# audio_board.net
KiCad netlist of a schematic drawn in EAGLE
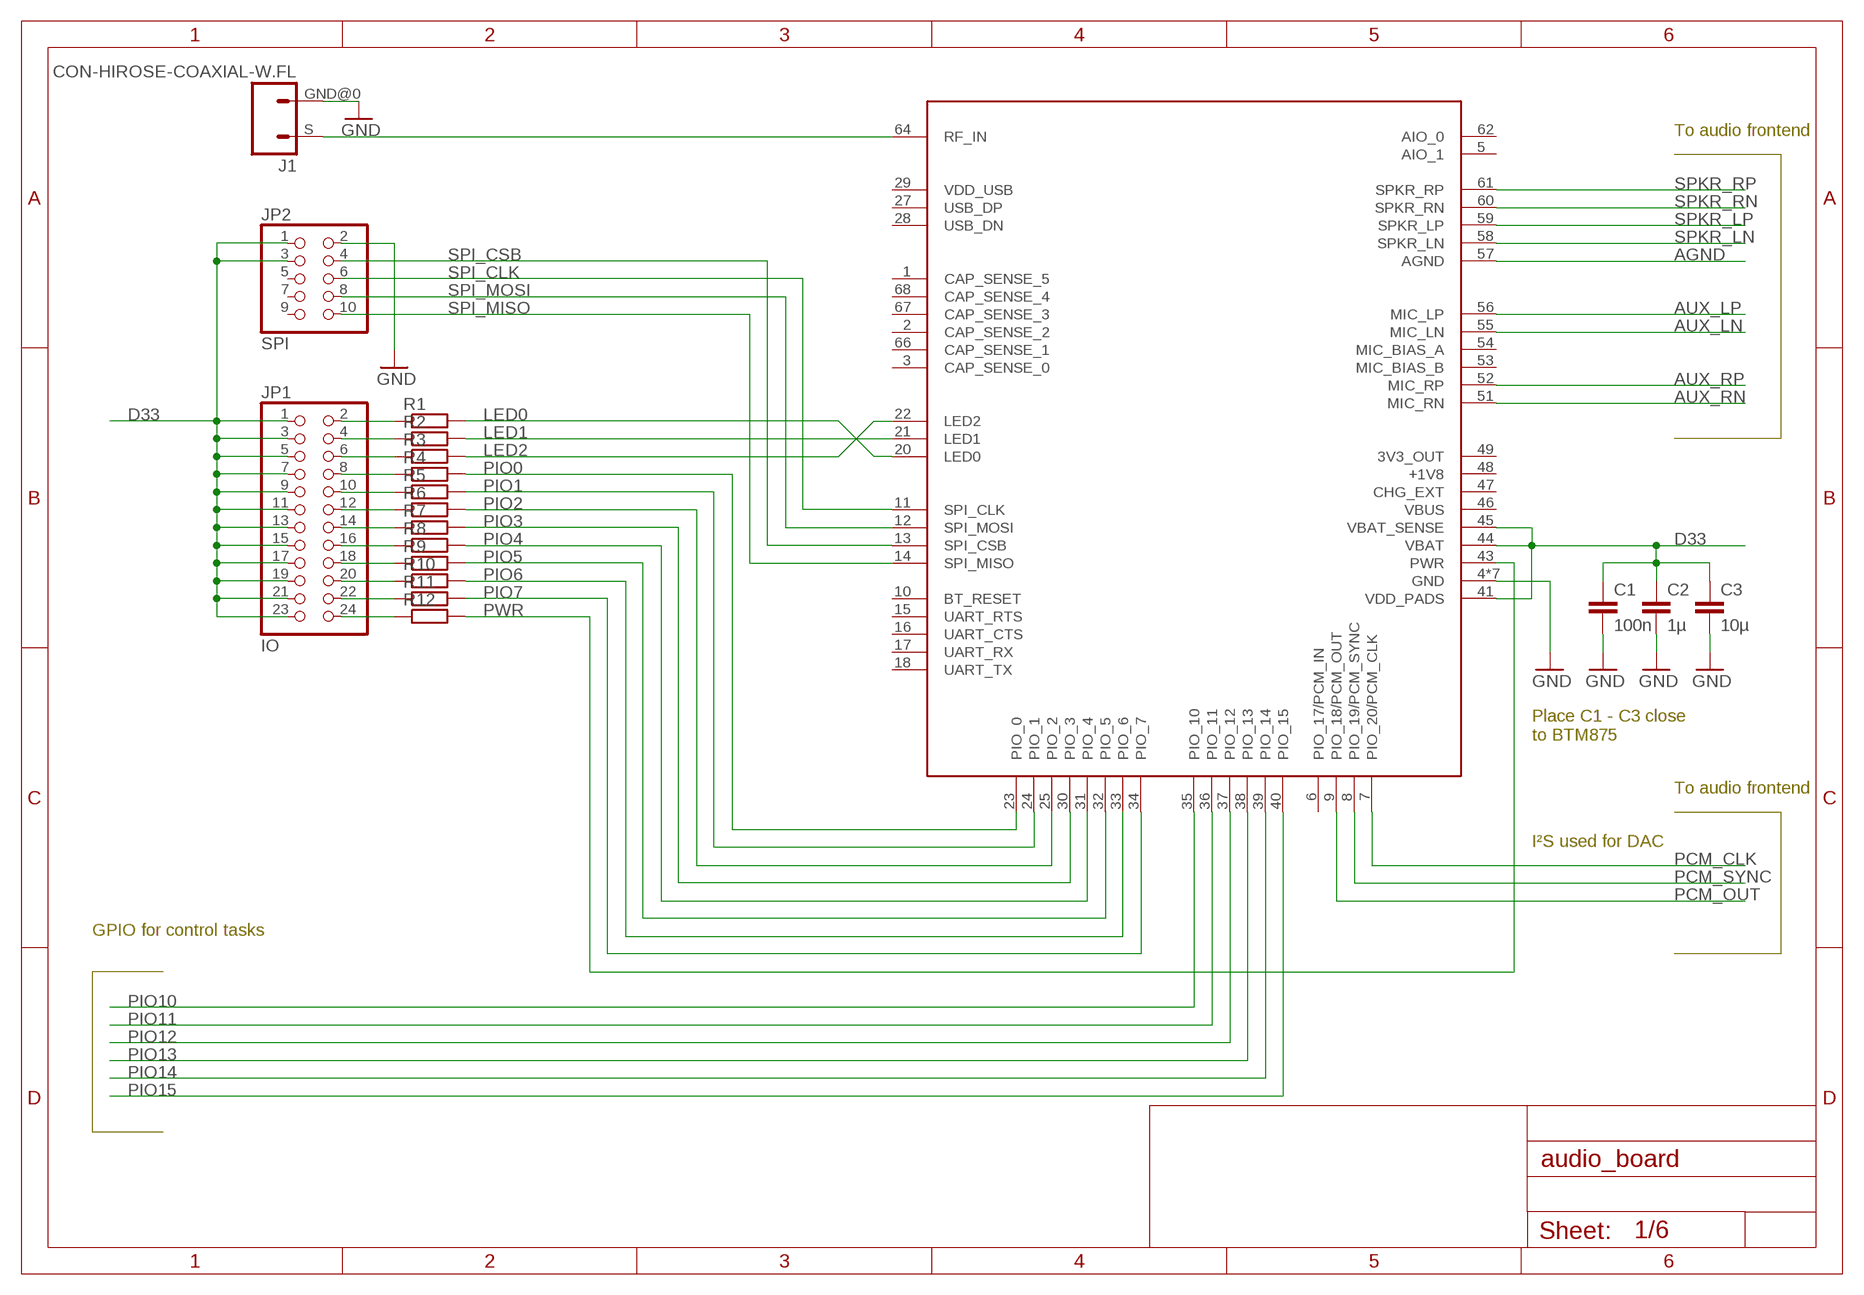
[diagram p0: schematic, sheet 1]
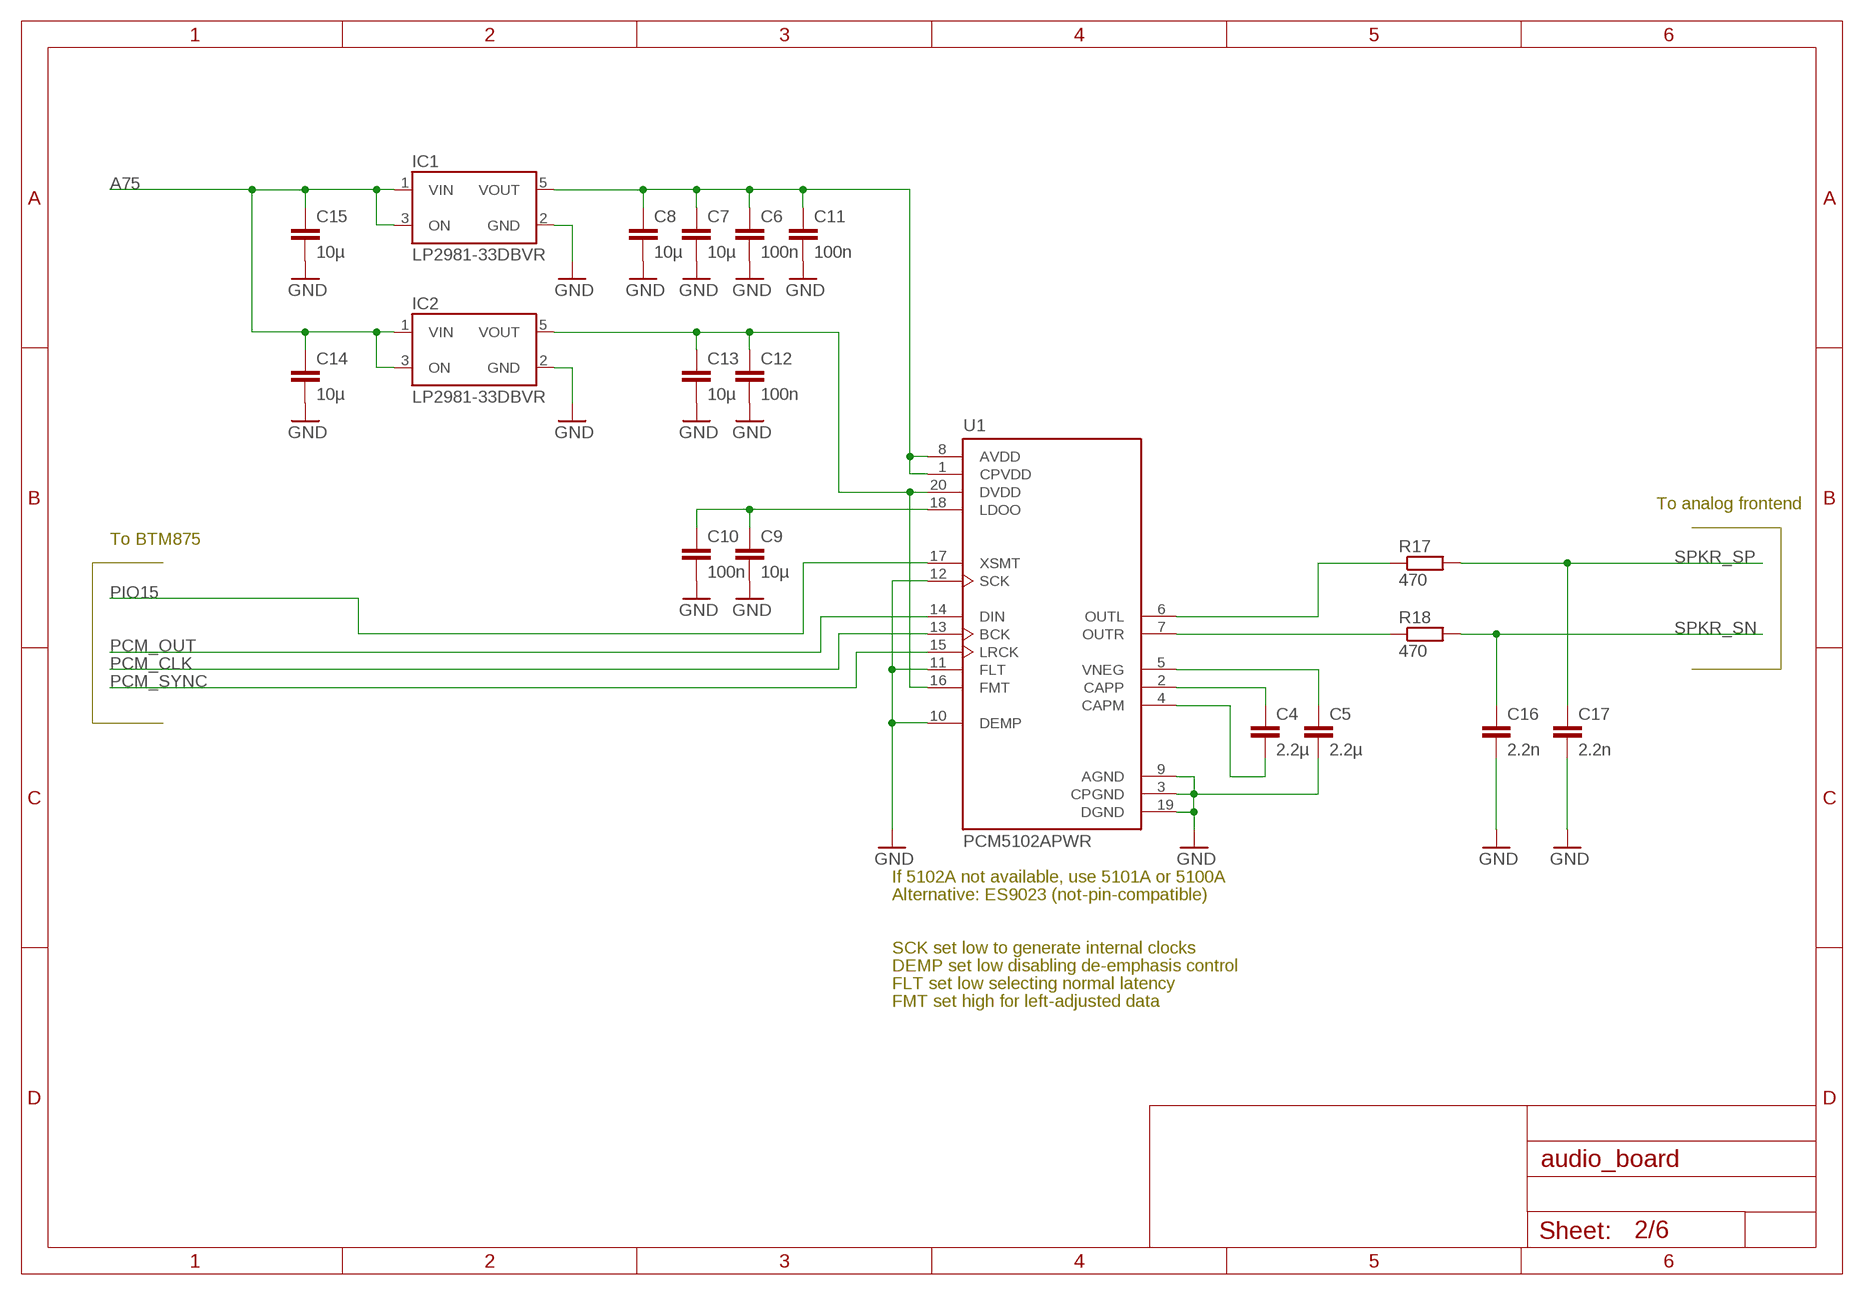
[diagram p1: schematic, sheet 2]
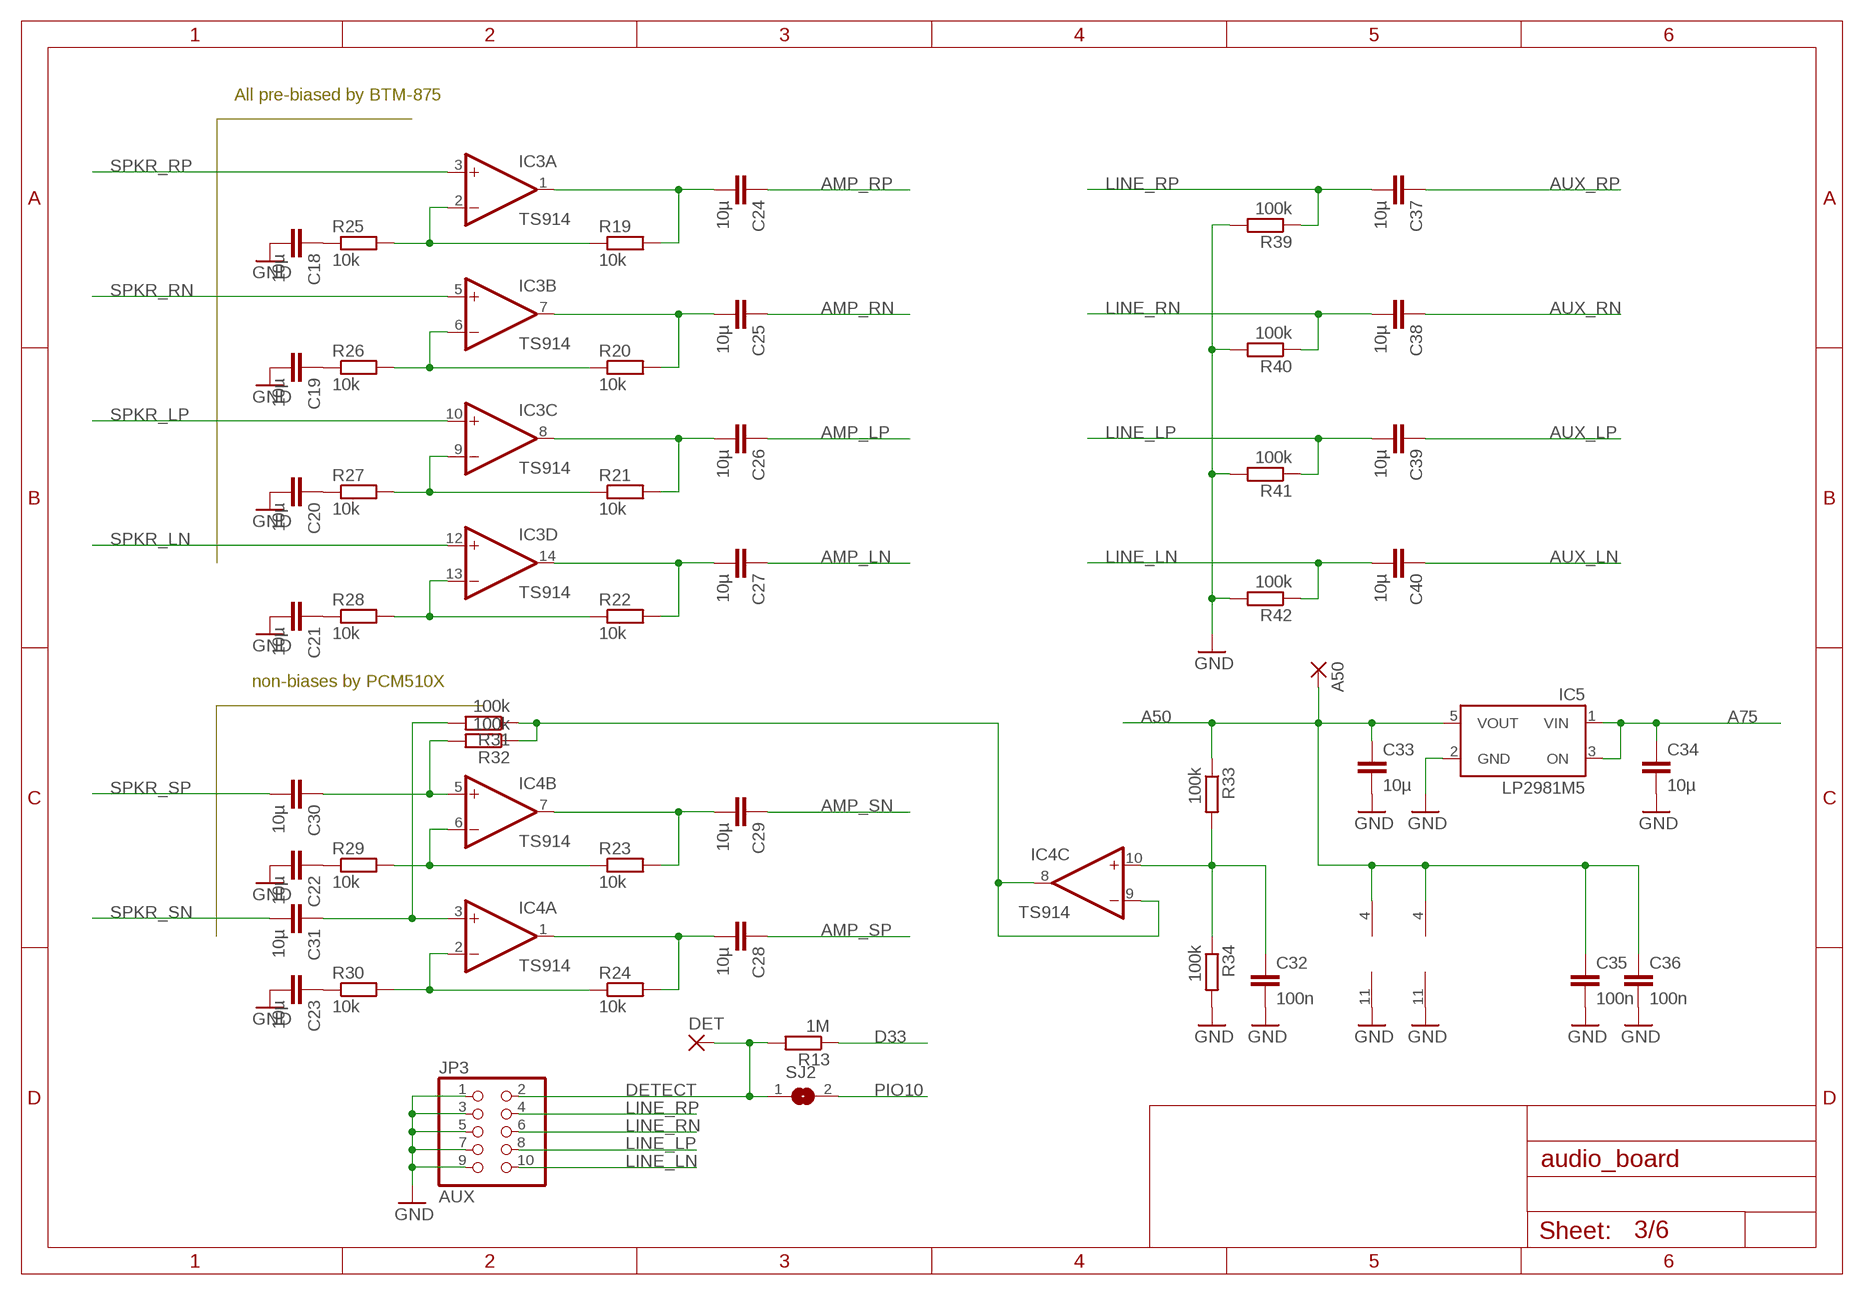
[diagram p2: schematic, sheet 3]
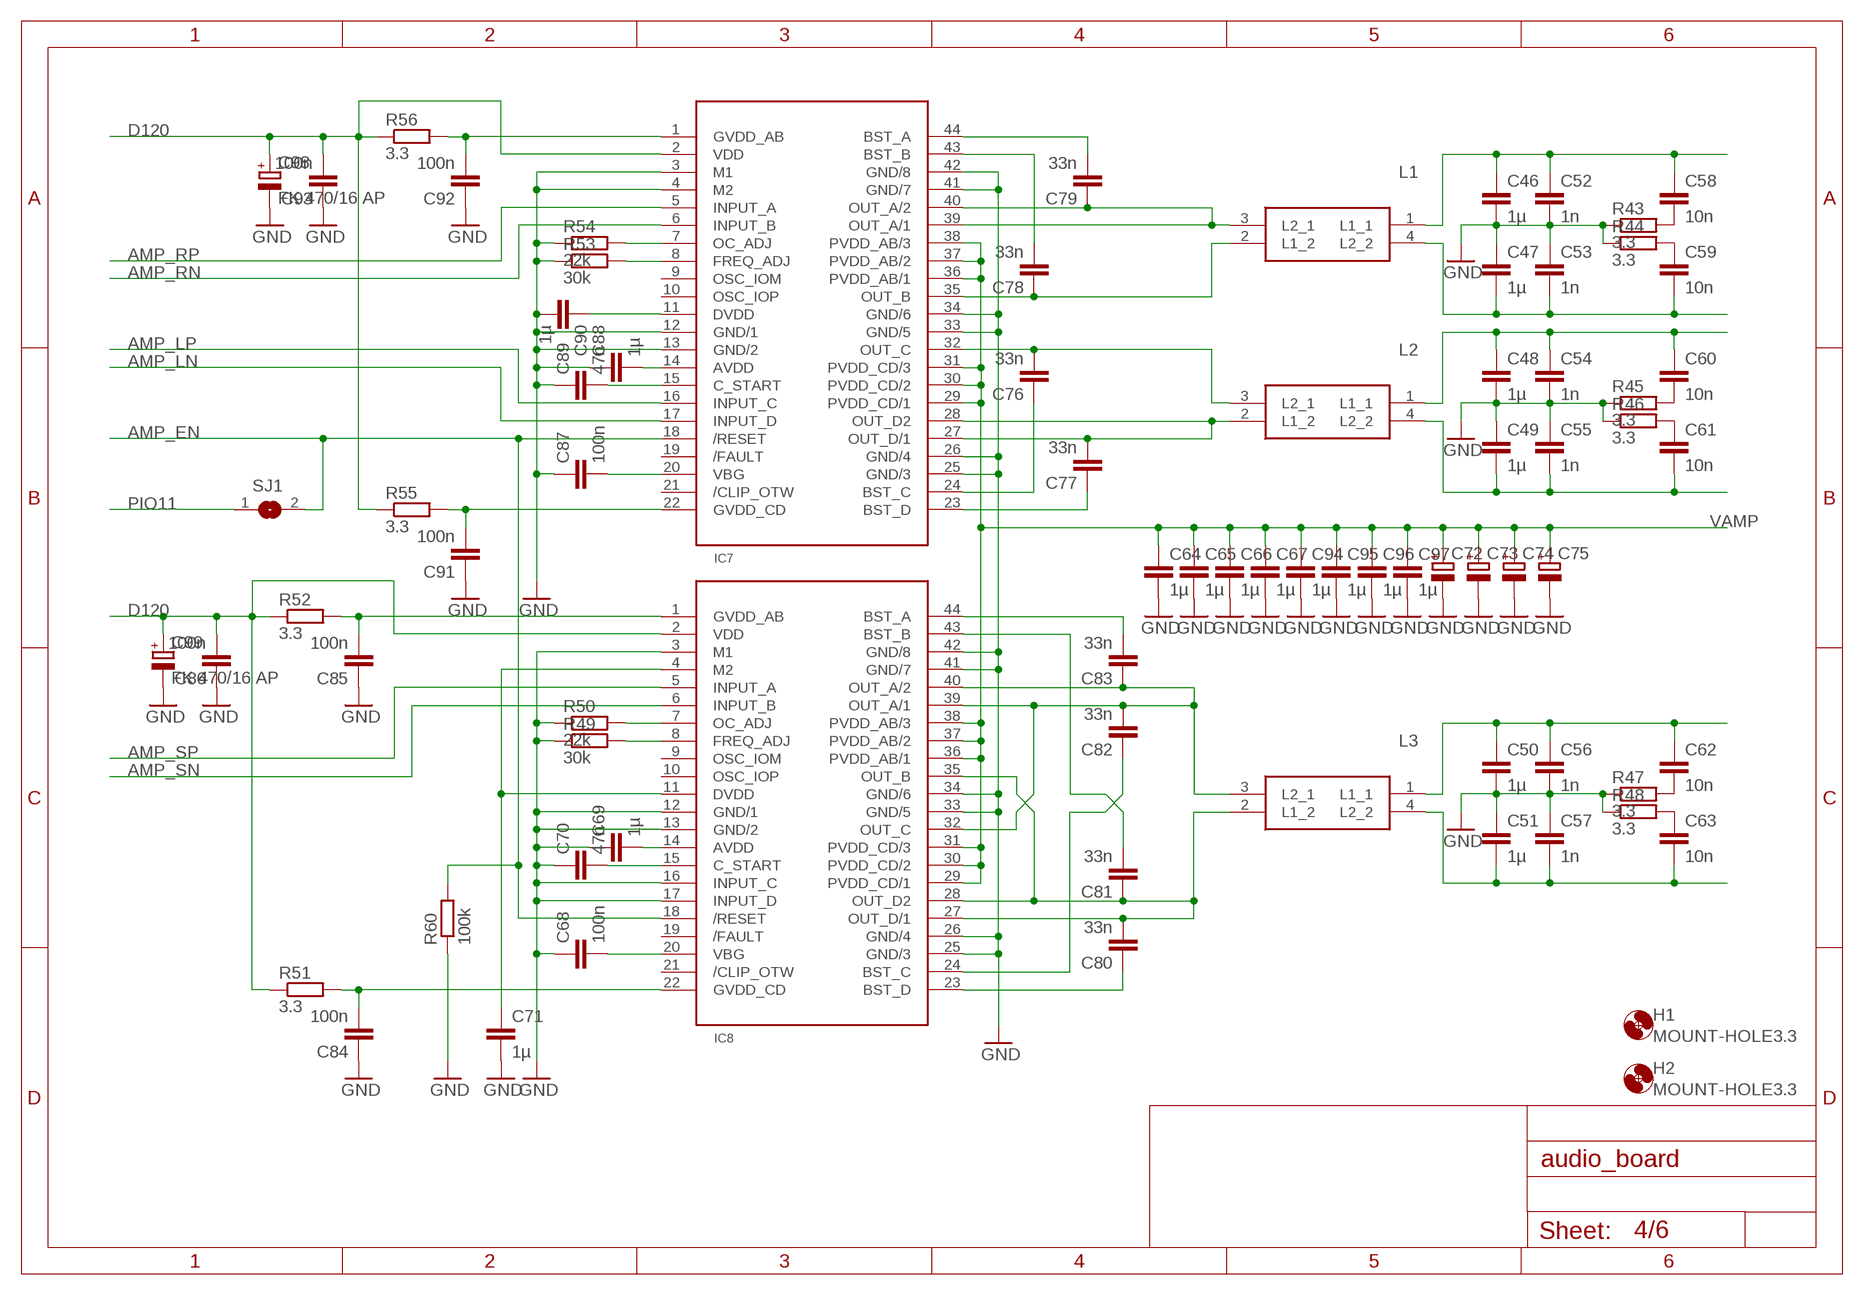
[diagram p3: schematic, sheet 4]
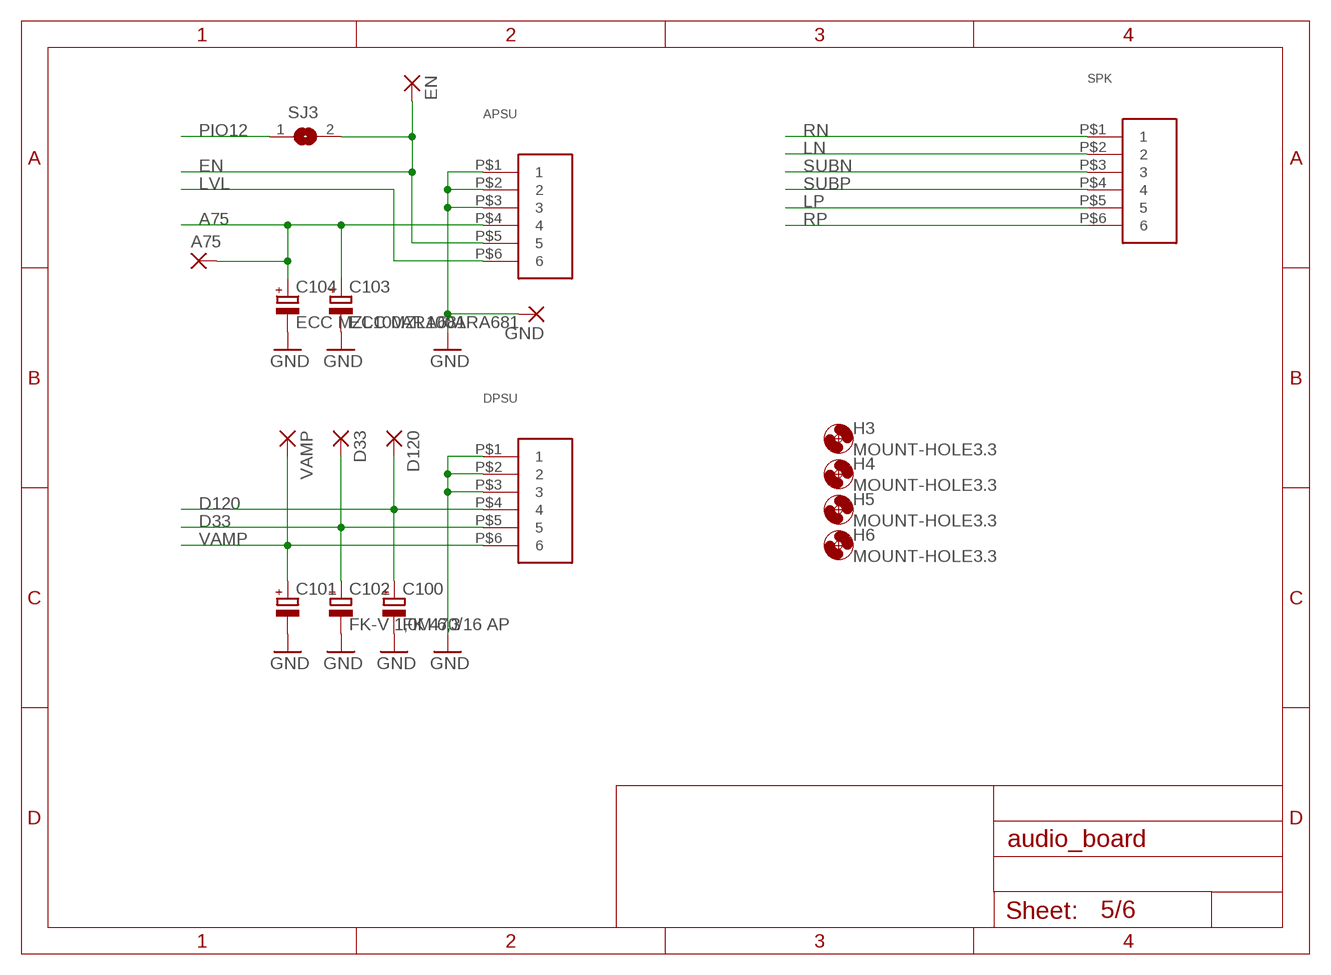
[diagram p4: schematic, sheet 5]
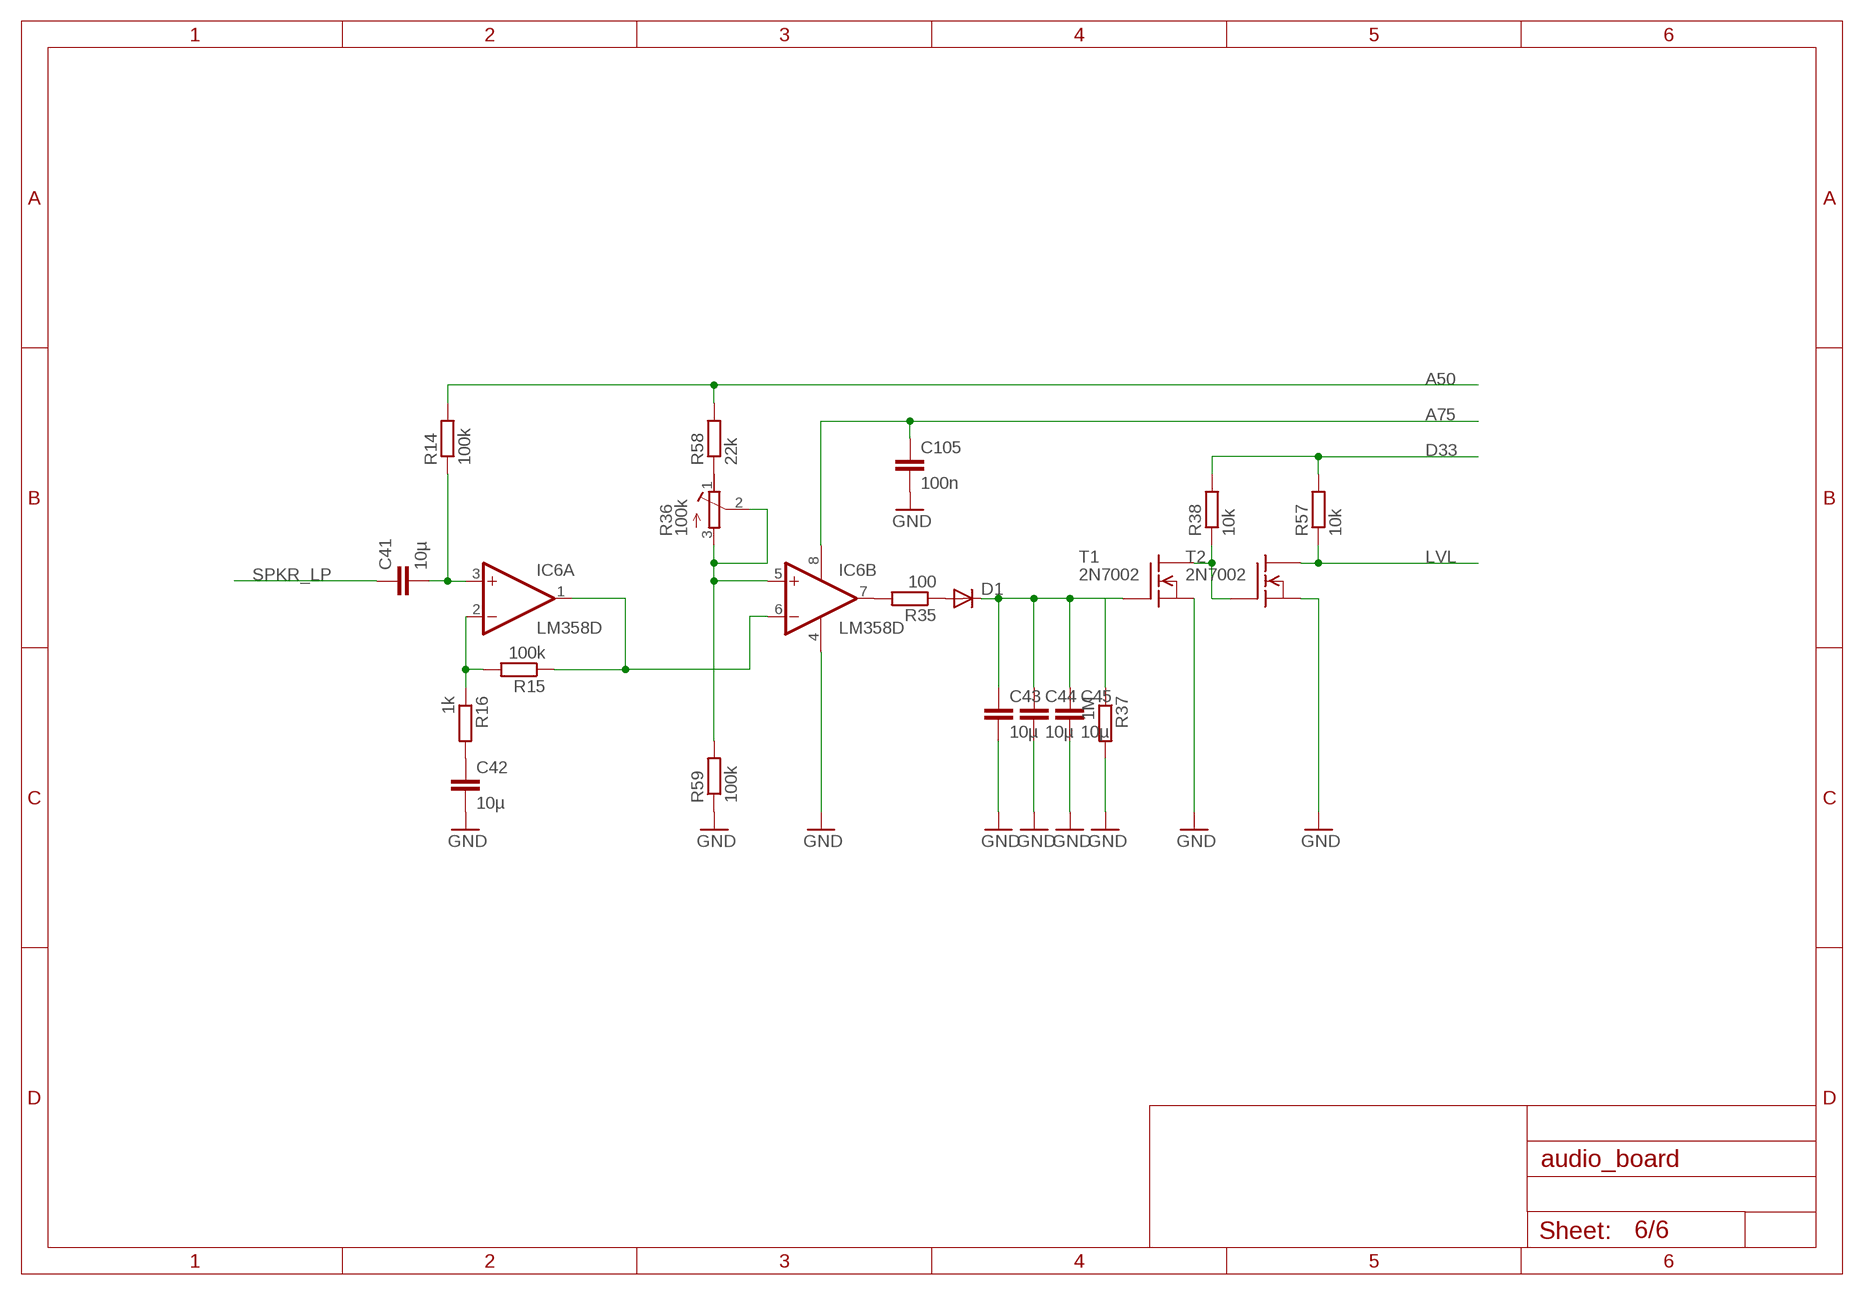
[diagram p5: schematic, sheet 6]

(export (version "E")
  (design (tool "Eeschema 10.0.6"))
  (components
    (comp (ref "C41")
      (value "10µ")
      (footprint "eagle-import:C0805")
      (libsource (lib "eagle-import") (part "C-EUC0805"))
    )
    (comp (ref "C42")
      (value "10µ")
      (footprint "eagle-import:C0805")
      (libsource (lib "eagle-import") (part "C-EUC0805"))
    )
    (comp (ref "C43")
      (value "10µ")
      (footprint "eagle-import:C0805")
      (libsource (lib "eagle-import") (part "C-EUC0805"))
    )
    (comp (ref "C44")
      (value "10µ")
      (footprint "eagle-import:C0805")
      (libsource (lib "eagle-import") (part "C-EUC0805"))
    )
    (comp (ref "C45")
      (value "10µ")
      (footprint "eagle-import:C0805")
      (libsource (lib "eagle-import") (part "C-EUC0805"))
    )
    (comp (ref "C105")
      (value "100n")
      (footprint "eagle-import:C0805")
      (libsource (lib "eagle-import") (part "C-EUC0805"))
    )
    (comp (ref "D1")
      (value "DIODE-DO214AC")
      (footprint "eagle-import:DO214AC")
      (libsource (lib "eagle-import") (part "DIODE-DO214AC"))
    )
    (comp (ref "IC6")
      (value "LM358D")
      (footprint "eagle-import:SO08")
      (libsource (lib "eagle-import") (part "LM358D"))
    )
    (comp (ref "R14")
      (value "100k")
      (footprint "eagle-import:M0805")
      (libsource (lib "eagle-import") (part "R-EU_M0805"))
    )
    (comp (ref "R15")
      (value "100k")
      (footprint "eagle-import:M0805")
      (libsource (lib "eagle-import") (part "R-EU_M0805"))
    )
    (comp (ref "R16")
      (value "1k")
      (footprint "eagle-import:M0805")
      (libsource (lib "eagle-import") (part "R-EU_M0805"))
    )
    (comp (ref "R35")
      (value "100")
      (footprint "eagle-import:M0805")
      (libsource (lib "eagle-import") (part "R-EU_M0805"))
    )
    (comp (ref "R36")
      (value "100k")
      (footprint "eagle-import:RTRIM3314G")
      (libsource (lib "eagle-import") (part "R-TRIMM3314G"))
    )
    (comp (ref "R37")
      (value "1M")
      (footprint "eagle-import:M0805")
      (libsource (lib "eagle-import") (part "R-EU_M0805"))
    )
    (comp (ref "R38")
      (value "10k")
      (footprint "eagle-import:M0805")
      (libsource (lib "eagle-import") (part "R-EU_M0805"))
    )
    (comp (ref "R57")
      (value "10k")
      (footprint "eagle-import:M0805")
      (libsource (lib "eagle-import") (part "R-EU_M0805"))
    )
    (comp (ref "R58")
      (value "22k")
      (footprint "eagle-import:M0805")
      (libsource (lib "eagle-import") (part "R-EU_M0805"))
    )
    (comp (ref "R59")
      (value "100k")
      (footprint "eagle-import:M0805")
      (libsource (lib "eagle-import") (part "R-EU_M0805"))
    )
    (comp (ref "T1")
      (value "2N7002")
      (footprint "eagle-import:SOT23")
      (libsource (lib "eagle-import") (part "2N7002"))
    )
    (comp (ref "T2")
      (value "2N7002")
      (footprint "eagle-import:SOT23")
      (libsource (lib "eagle-import") (part "2N7002"))
    )
    (comp (ref "BT1")
      (value "BTM875-B")
      (footprint "eagle-import:BTM875")
      (libsource (lib "eagle-import") (part "BTM875-B"))
    )
    (comp (ref "C1")
      (value "100n")
      (footprint "eagle-import:C0805")
      (libsource (lib "eagle-import") (part "C-EUC0805"))
    )
    (comp (ref "C2")
      (value "1µ")
      (footprint "eagle-import:C0805")
      (libsource (lib "eagle-import") (part "C-EUC0805"))
    )
    (comp (ref "C3")
      (value "10µ")
      (footprint "eagle-import:C0805")
      (libsource (lib "eagle-import") (part "C-EUC0805"))
    )
    (comp (ref "J1")
      (value "CON-HIROSE-COAXIAL-W.FL")
      (footprint "eagle-import:CON-W.FL")
      (libsource (lib "eagle-import") (part "CON-HIROSE-COAXIAL-W.FL"))
    )
    (comp (ref "JP1")
      (value "IO")
      (footprint "eagle-import:2X12")
      (libsource (lib "eagle-import") (part "PINHD-2X12"))
    )
    (comp (ref "JP2")
      (value "SPI")
      (footprint "eagle-import:2X05")
      (libsource (lib "eagle-import") (part "PINHD-2X5"))
    )
    (comp (ref "R1")
      (value "R-EU_R0805")
      (footprint "eagle-import:R0805")
      (libsource (lib "eagle-import") (part "R-EU_R0805"))
    )
    (comp (ref "R2")
      (value "R-EU_R0805")
      (footprint "eagle-import:R0805")
      (libsource (lib "eagle-import") (part "R-EU_R0805"))
    )
    (comp (ref "R3")
      (value "R-EU_R0805")
      (footprint "eagle-import:R0805")
      (libsource (lib "eagle-import") (part "R-EU_R0805"))
    )
    (comp (ref "R4")
      (value "R-EU_R0805")
      (footprint "eagle-import:R0805")
      (libsource (lib "eagle-import") (part "R-EU_R0805"))
    )
    (comp (ref "R5")
      (value "R-EU_R0805")
      (footprint "eagle-import:R0805")
      (libsource (lib "eagle-import") (part "R-EU_R0805"))
    )
    (comp (ref "R6")
      (value "R-EU_R0805")
      (footprint "eagle-import:R0805")
      (libsource (lib "eagle-import") (part "R-EU_R0805"))
    )
    (comp (ref "R7")
      (value "R-EU_R0805")
      (footprint "eagle-import:R0805")
      (libsource (lib "eagle-import") (part "R-EU_R0805"))
    )
    (comp (ref "R8")
      (value "R-EU_R0805")
      (footprint "eagle-import:R0805")
      (libsource (lib "eagle-import") (part "R-EU_R0805"))
    )
    (comp (ref "R9")
      (value "R-EU_R0805")
      (footprint "eagle-import:R0805")
      (libsource (lib "eagle-import") (part "R-EU_R0805"))
    )
    (comp (ref "R10")
      (value "R-EU_R0805")
      (footprint "eagle-import:R0805")
      (libsource (lib "eagle-import") (part "R-EU_R0805"))
    )
    (comp (ref "R11")
      (value "R-EU_R0805")
      (footprint "eagle-import:R0805")
      (libsource (lib "eagle-import") (part "R-EU_R0805"))
    )
    (comp (ref "R12")
      (value "R-EU_R0805")
      (footprint "eagle-import:R0805")
      (libsource (lib "eagle-import") (part "R-EU_R0805"))
    )
    (comp (ref "C46")
      (value "1µ")
      (footprint "eagle-import:C050-075X075")
      (libsource (lib "eagle-import") (part "C-EU050-075X075"))
    )
    (comp (ref "C47")
      (value "1µ")
      (footprint "eagle-import:C050-075X075")
      (libsource (lib "eagle-import") (part "C-EU050-075X075"))
    )
    (comp (ref "C48")
      (value "1µ")
      (footprint "eagle-import:C050-075X075")
      (libsource (lib "eagle-import") (part "C-EU050-075X075"))
    )
    (comp (ref "C49")
      (value "1µ")
      (footprint "eagle-import:C050-075X075")
      (libsource (lib "eagle-import") (part "C-EU050-075X075"))
    )
    (comp (ref "C50")
      (value "1µ")
      (footprint "eagle-import:C050-075X075")
      (libsource (lib "eagle-import") (part "C-EU050-075X075"))
    )
    (comp (ref "C51")
      (value "1µ")
      (footprint "eagle-import:C050-075X075")
      (libsource (lib "eagle-import") (part "C-EU050-075X075"))
    )
    (comp (ref "C52")
      (value "1n")
      (footprint "eagle-import:C0805")
      (libsource (lib "eagle-import") (part "C-EUC0805"))
    )
    (comp (ref "C53")
      (value "1n")
      (footprint "eagle-import:C0805")
      (libsource (lib "eagle-import") (part "C-EUC0805"))
    )
    (comp (ref "C54")
      (value "1n")
      (footprint "eagle-import:C0805")
      (libsource (lib "eagle-import") (part "C-EUC0805"))
    )
    (comp (ref "C55")
      (value "1n")
      (footprint "eagle-import:C0805")
      (libsource (lib "eagle-import") (part "C-EUC0805"))
    )
    (comp (ref "C56")
      (value "1n")
      (footprint "eagle-import:C0805")
      (libsource (lib "eagle-import") (part "C-EUC0805"))
    )
    (comp (ref "C57")
      (value "1n")
      (footprint "eagle-import:C0805")
      (libsource (lib "eagle-import") (part "C-EUC0805"))
    )
    (comp (ref "C58")
      (value "10n")
      (footprint "eagle-import:C0805")
      (libsource (lib "eagle-import") (part "C-EUC0805"))
    )
    (comp (ref "C59")
      (value "10n")
      (footprint "eagle-import:C0805")
      (libsource (lib "eagle-import") (part "C-EUC0805"))
    )
    (comp (ref "C60")
      (value "10n")
      (footprint "eagle-import:C0805")
      (libsource (lib "eagle-import") (part "C-EUC0805"))
    )
    (comp (ref "C61")
      (value "10n")
      (footprint "eagle-import:C0805")
      (libsource (lib "eagle-import") (part "C-EUC0805"))
    )
    (comp (ref "C62")
      (value "10n")
      (footprint "eagle-import:C0805")
      (libsource (lib "eagle-import") (part "C-EUC0805"))
    )
    (comp (ref "C63")
      (value "10n")
      (footprint "eagle-import:C0805")
      (libsource (lib "eagle-import") (part "C-EUC0805"))
    )
    (comp (ref "C64")
      (value "1µ")
      (footprint "eagle-import:C0805")
      (libsource (lib "eagle-import") (part "C-EUC0805"))
    )
    (comp (ref "C65")
      (value "1µ")
      (footprint "eagle-import:C0805")
      (libsource (lib "eagle-import") (part "C-EUC0805"))
    )
    (comp (ref "C66")
      (value "1µ")
      (footprint "eagle-import:C0805")
      (libsource (lib "eagle-import") (part "C-EUC0805"))
    )
    (comp (ref "C67")
      (value "1µ")
      (footprint "eagle-import:C0805")
      (libsource (lib "eagle-import") (part "C-EUC0805"))
    )
    (comp (ref "C68")
      (value "100n")
      (footprint "eagle-import:C0805")
      (libsource (lib "eagle-import") (part "C-EUC0805"))
    )
    (comp (ref "C69")
      (value "1µ")
      (footprint "eagle-import:C0805")
      (libsource (lib "eagle-import") (part "C-EUC0805"))
    )
    (comp (ref "C70")
      (value "47n")
      (footprint "eagle-import:C0805")
      (libsource (lib "eagle-import") (part "C-EUC0805"))
    )
    (comp (ref "C71")
      (value "1µ")
      (footprint "eagle-import:C0805")
      (libsource (lib "eagle-import") (part "C-EUC0805"))
    )
    (comp (ref "C72")
      (value "CPOL-EU153CLV-0810")
      (footprint "eagle-import:153CLV-0810")
      (libsource (lib "eagle-import") (part "CPOL-EU153CLV-0810"))
    )
    (comp (ref "C73")
      (value "CPOL-EU153CLV-0810")
      (footprint "eagle-import:153CLV-0810")
      (libsource (lib "eagle-import") (part "CPOL-EU153CLV-0810"))
    )
    (comp (ref "C74")
      (value "CPOL-EU153CLV-0810")
      (footprint "eagle-import:153CLV-0810")
      (libsource (lib "eagle-import") (part "CPOL-EU153CLV-0810"))
    )
    (comp (ref "C75")
      (value "CPOL-EU153CLV-0810")
      (footprint "eagle-import:153CLV-0810")
      (libsource (lib "eagle-import") (part "CPOL-EU153CLV-0810"))
    )
    (comp (ref "C76")
      (value "33n")
      (footprint "eagle-import:C0805")
      (libsource (lib "eagle-import") (part "C-EUC0805"))
    )
    (comp (ref "C77")
      (value "33n")
      (footprint "eagle-import:C0805")
      (libsource (lib "eagle-import") (part "C-EUC0805"))
    )
    (comp (ref "C78")
      (value "33n")
      (footprint "eagle-import:C0805")
      (libsource (lib "eagle-import") (part "C-EUC0805"))
    )
    (comp (ref "C79")
      (value "33n")
      (footprint "eagle-import:C0805")
      (libsource (lib "eagle-import") (part "C-EUC0805"))
    )
    (comp (ref "C80")
      (value "33n")
      (footprint "eagle-import:C0805")
      (libsource (lib "eagle-import") (part "C-EUC0805"))
    )
    (comp (ref "C81")
      (value "33n")
      (footprint "eagle-import:C0805")
      (libsource (lib "eagle-import") (part "C-EUC0805"))
    )
    (comp (ref "C82")
      (value "33n")
      (footprint "eagle-import:C0805")
      (libsource (lib "eagle-import") (part "C-EUC0805"))
    )
    (comp (ref "C83")
      (value "33n")
      (footprint "eagle-import:C0805")
      (libsource (lib "eagle-import") (part "C-EUC0805"))
    )
    (comp (ref "C84")
      (value "100n")
      (footprint "eagle-import:C0805")
      (libsource (lib "eagle-import") (part "C-EUC0805"))
    )
    (comp (ref "C85")
      (value "100n")
      (footprint "eagle-import:C0805")
      (libsource (lib "eagle-import") (part "C-EUC0805"))
    )
    (comp (ref "C86")
      (value "100n")
      (footprint "eagle-import:C0805")
      (libsource (lib "eagle-import") (part "C-EUC0805"))
    )
    (comp (ref "C87")
      (value "100n")
      (footprint "eagle-import:C0805")
      (libsource (lib "eagle-import") (part "C-EUC0805"))
    )
    (comp (ref "C88")
      (value "1µ")
      (footprint "eagle-import:C0805")
      (libsource (lib "eagle-import") (part "C-EUC0805"))
    )
    (comp (ref "C89")
      (value "47n")
      (footprint "eagle-import:C0805")
      (libsource (lib "eagle-import") (part "C-EUC0805"))
    )
    (comp (ref "C90")
      (value "1µ")
      (footprint "eagle-import:C0805")
      (libsource (lib "eagle-import") (part "C-EUC0805"))
    )
    (comp (ref "C91")
      (value "100n")
      (footprint "eagle-import:C0805")
      (libsource (lib "eagle-import") (part "C-EUC0805"))
    )
    (comp (ref "C92")
      (value "100n")
      (footprint "eagle-import:C0805")
      (libsource (lib "eagle-import") (part "C-EUC0805"))
    )
    (comp (ref "C93")
      (value "100n")
      (footprint "eagle-import:C0805")
      (libsource (lib "eagle-import") (part "C-EUC0805"))
    )
    (comp (ref "C94")
      (value "1µ")
      (footprint "eagle-import:C0805")
      (libsource (lib "eagle-import") (part "C-EUC0805"))
    )
    (comp (ref "C95")
      (value "1µ")
      (footprint "eagle-import:C0805")
      (libsource (lib "eagle-import") (part "C-EUC0805"))
    )
    (comp (ref "C96")
      (value "1µ")
      (footprint "eagle-import:C0805")
      (libsource (lib "eagle-import") (part "C-EUC0805"))
    )
    (comp (ref "C97")
      (value "1µ")
      (footprint "eagle-import:C0805")
      (libsource (lib "eagle-import") (part "C-EUC0805"))
    )
    (comp (ref "C98")
      (value "FK 470/16 AP")
      (footprint "eagle-import:153CLV-0810")
      (libsource (lib "eagle-import") (part "CPOL-EU153CLV-0810"))
    )
    (comp (ref "C99")
      (value "FK 470/16 AP")
      (footprint "eagle-import:153CLV-0810")
      (libsource (lib "eagle-import") (part "CPOL-EU153CLV-0810"))
    )
    (comp (ref "H1")
      (value "MOUNT-HOLE3.3")
      (footprint "eagle-import:3,3")
      (libsource (lib "eagle-import") (part "MOUNT-HOLE3.3"))
    )
    (comp (ref "H2")
      (value "MOUNT-HOLE3.3")
      (footprint "eagle-import:3,3")
      (libsource (lib "eagle-import") (part "MOUNT-HOLE3.3"))
    )
    (comp (ref "IC7")
      (value "TPA3255")
      (footprint "eagle-import:POWERPAD-TSSOP-44")
      (libsource (lib "eagle-import") (part "TPA3255"))
    )
    (comp (ref "IC8")
      (value "TPA3255")
      (footprint "eagle-import:POWERPAD-TSSOP-44")
      (libsource (lib "eagle-import") (part "TPA3255"))
    )
    (comp (ref "L1")
      (value "UA8014-ALD")
      (footprint "eagle-import:UA8014ALD")
      (fields (field (name "MOUSER_PART_NUMBER") "994-UA8014-ALD"))
      (libsource (lib "eagle-import") (part "UA8014-ALD"))
    )
    (comp (ref "L2")
      (value "UA8014-ALD")
      (footprint "eagle-import:UA8014ALD")
      (fields (field (name "MOUSER_PART_NUMBER") "994-UA8014-ALD"))
      (libsource (lib "eagle-import") (part "UA8014-ALD"))
    )
    (comp (ref "L3")
      (value "UA8014-ALD")
      (footprint "eagle-import:UA8014ALD")
      (fields (field (name "MOUSER_PART_NUMBER") "994-UA8014-ALD"))
      (libsource (lib "eagle-import") (part "UA8014-ALD"))
    )
    (comp (ref "R43")
      (value "3.3")
      (footprint "eagle-import:R0805")
      (libsource (lib "eagle-import") (part "R-EU_R0805"))
    )
    (comp (ref "R44")
      (value "3.3")
      (footprint "eagle-import:R0805")
      (libsource (lib "eagle-import") (part "R-EU_R0805"))
    )
    (comp (ref "R45")
      (value "3.3")
      (footprint "eagle-import:R0805")
      (libsource (lib "eagle-import") (part "R-EU_R0805"))
    )
    (comp (ref "R46")
      (value "3.3")
      (footprint "eagle-import:R0805")
      (libsource (lib "eagle-import") (part "R-EU_R0805"))
    )
    (comp (ref "R47")
      (value "3.3")
      (footprint "eagle-import:R0805")
      (libsource (lib "eagle-import") (part "R-EU_R0805"))
    )
    (comp (ref "R48")
      (value "3.3")
      (footprint "eagle-import:R0805")
      (libsource (lib "eagle-import") (part "R-EU_R0805"))
    )
    (comp (ref "R49")
      (value "30k")
      (footprint "eagle-import:R0805")
      (libsource (lib "eagle-import") (part "R-EU_R0805"))
    )
    (comp (ref "R50")
      (value "22k")
      (footprint "eagle-import:R0805")
      (libsource (lib "eagle-import") (part "R-EU_R0805"))
    )
    (comp (ref "R51")
      (value "3.3")
      (footprint "eagle-import:R0805")
      (libsource (lib "eagle-import") (part "R-EU_R0805"))
    )
    (comp (ref "R52")
      (value "3.3")
      (footprint "eagle-import:R0805")
      (libsource (lib "eagle-import") (part "R-EU_R0805"))
    )
    (comp (ref "R53")
      (value "30k")
      (footprint "eagle-import:R0805")
      (libsource (lib "eagle-import") (part "R-EU_R0805"))
    )
    (comp (ref "R54")
      (value "22k")
      (footprint "eagle-import:R0805")
      (libsource (lib "eagle-import") (part "R-EU_R0805"))
    )
    (comp (ref "R55")
      (value "3.3")
      (footprint "eagle-import:R0805")
      (libsource (lib "eagle-import") (part "R-EU_R0805"))
    )
    (comp (ref "R56")
      (value "3.3")
      (footprint "eagle-import:R0805")
      (libsource (lib "eagle-import") (part "R-EU_R0805"))
    )
    (comp (ref "R60")
      (value "100k")
      (footprint "eagle-import:R0805")
      (libsource (lib "eagle-import") (part "R-EU_R0805"))
    )
    (comp (ref "SJ1") (value "SJ") (footprint "eagle-import:SJ") (libsource (lib "eagle-import") (part "SJ")))
    (comp (ref "A50")
      (value "SMD2")
      (footprint "eagle-import:SMD1,27-2,54")
      (libsource (lib "eagle-import") (part "SMD2"))
    )
    (comp (ref "C18")
      (value "10µ")
      (footprint "eagle-import:C0805")
      (libsource (lib "eagle-import") (part "C-EUC0805"))
    )
    (comp (ref "C19")
      (value "10µ")
      (footprint "eagle-import:C0805")
      (libsource (lib "eagle-import") (part "C-EUC0805"))
    )
    (comp (ref "C20")
      (value "10µ")
      (footprint "eagle-import:C0805")
      (libsource (lib "eagle-import") (part "C-EUC0805"))
    )
    (comp (ref "C21")
      (value "10µ")
      (footprint "eagle-import:C0805")
      (libsource (lib "eagle-import") (part "C-EUC0805"))
    )
    (comp (ref "C22")
      (value "10µ")
      (footprint "eagle-import:C0805")
      (libsource (lib "eagle-import") (part "C-EUC0805"))
    )
    (comp (ref "C23")
      (value "10µ")
      (footprint "eagle-import:C0805")
      (libsource (lib "eagle-import") (part "C-EUC0805"))
    )
    (comp (ref "C24")
      (value "10µ")
      (footprint "eagle-import:C0805")
      (libsource (lib "eagle-import") (part "C-EUC0805"))
    )
    (comp (ref "C25")
      (value "10µ")
      (footprint "eagle-import:C0805")
      (libsource (lib "eagle-import") (part "C-EUC0805"))
    )
    (comp (ref "C26")
      (value "10µ")
      (footprint "eagle-import:C0805")
      (libsource (lib "eagle-import") (part "C-EUC0805"))
    )
    (comp (ref "C27")
      (value "10µ")
      (footprint "eagle-import:C0805")
      (libsource (lib "eagle-import") (part "C-EUC0805"))
    )
    (comp (ref "C28")
      (value "10µ")
      (footprint "eagle-import:C0805")
      (libsource (lib "eagle-import") (part "C-EUC0805"))
    )
    (comp (ref "C29")
      (value "10µ")
      (footprint "eagle-import:C0805")
      (libsource (lib "eagle-import") (part "C-EUC0805"))
    )
    (comp (ref "C30")
      (value "10µ")
      (footprint "eagle-import:C0805")
      (libsource (lib "eagle-import") (part "C-EUC0805"))
    )
    (comp (ref "C31")
      (value "10µ")
      (footprint "eagle-import:C0805")
      (libsource (lib "eagle-import") (part "C-EUC0805"))
    )
    (comp (ref "C32")
      (value "100n")
      (footprint "eagle-import:C0805")
      (libsource (lib "eagle-import") (part "C-EUC0805"))
    )
    (comp (ref "C33")
      (value "10µ")
      (footprint "eagle-import:C0805")
      (libsource (lib "eagle-import") (part "C-EUC0805"))
    )
    (comp (ref "C34")
      (value "10µ")
      (footprint "eagle-import:C0805")
      (libsource (lib "eagle-import") (part "C-EUC0805"))
    )
    (comp (ref "C35")
      (value "100n")
      (footprint "eagle-import:C0805")
      (libsource (lib "eagle-import") (part "C-EUC0805"))
    )
    (comp (ref "C36")
      (value "100n")
      (footprint "eagle-import:C0805")
      (libsource (lib "eagle-import") (part "C-EUC0805"))
    )
    (comp (ref "C37")
      (value "10µ")
      (footprint "eagle-import:C0805")
      (libsource (lib "eagle-import") (part "C-EUC0805"))
    )
    (comp (ref "C38")
      (value "10µ")
      (footprint "eagle-import:C0805")
      (libsource (lib "eagle-import") (part "C-EUC0805"))
    )
    (comp (ref "C39")
      (value "10µ")
      (footprint "eagle-import:C0805")
      (libsource (lib "eagle-import") (part "C-EUC0805"))
    )
    (comp (ref "C40")
      (value "10µ")
      (footprint "eagle-import:C0805")
      (libsource (lib "eagle-import") (part "C-EUC0805"))
    )
    (comp (ref "DET")
      (value "SMD2")
      (footprint "eagle-import:SMD1,27-2,54")
      (libsource (lib "eagle-import") (part "SMD2"))
    )
    (comp (ref "IC3")
      (value "TS914")
      (footprint "eagle-import:SO14")
      (libsource (lib "eagle-import") (part "LM324D"))
    )
    (comp (ref "IC4")
      (value "TS914")
      (footprint "eagle-import:SO14")
      (libsource (lib "eagle-import") (part "LM324D"))
    )
    (comp (ref "IC5")
      (value "LP2981M5")
      (footprint "eagle-import:SOT23-5")
      (libsource (lib "eagle-import") (part "LP2981M5"))
    )
    (comp (ref "JP3")
      (value "AUX")
      (footprint "eagle-import:2X05")
      (libsource (lib "eagle-import") (part "PINHD-2X5"))
    )
    (comp (ref "R13")
      (value "1M")
      (footprint "eagle-import:R0805")
      (libsource (lib "eagle-import") (part "R-EU_R0805"))
    )
    (comp (ref "R19")
      (value "10k")
      (footprint "eagle-import:R0805")
      (libsource (lib "eagle-import") (part "R-EU_R0805"))
    )
    (comp (ref "R20")
      (value "10k")
      (footprint "eagle-import:R0805")
      (libsource (lib "eagle-import") (part "R-EU_R0805"))
    )
    (comp (ref "R21")
      (value "10k")
      (footprint "eagle-import:R0805")
      (libsource (lib "eagle-import") (part "R-EU_R0805"))
    )
    (comp (ref "R22")
      (value "10k")
      (footprint "eagle-import:R0805")
      (libsource (lib "eagle-import") (part "R-EU_R0805"))
    )
    (comp (ref "R23")
      (value "10k")
      (footprint "eagle-import:R0805")
      (libsource (lib "eagle-import") (part "R-EU_R0805"))
    )
    (comp (ref "R24")
      (value "10k")
      (footprint "eagle-import:R0805")
      (libsource (lib "eagle-import") (part "R-EU_R0805"))
    )
    (comp (ref "R25")
      (value "10k")
      (footprint "eagle-import:R0805")
      (libsource (lib "eagle-import") (part "R-EU_R0805"))
    )
    (comp (ref "R26")
      (value "10k")
      (footprint "eagle-import:R0805")
      (libsource (lib "eagle-import") (part "R-EU_R0805"))
    )
    (comp (ref "R27")
      (value "10k")
      (footprint "eagle-import:R0805")
      (libsource (lib "eagle-import") (part "R-EU_R0805"))
    )
    (comp (ref "R28")
      (value "10k")
      (footprint "eagle-import:R0805")
      (libsource (lib "eagle-import") (part "R-EU_R0805"))
    )
    (comp (ref "R29")
      (value "10k")
      (footprint "eagle-import:R0805")
      (libsource (lib "eagle-import") (part "R-EU_R0805"))
    )
    (comp (ref "R30")
      (value "10k")
      (footprint "eagle-import:R0805")
      (libsource (lib "eagle-import") (part "R-EU_R0805"))
    )
    (comp (ref "R31")
      (value "100k")
      (footprint "eagle-import:R0805")
      (libsource (lib "eagle-import") (part "R-EU_R0805"))
    )
    (comp (ref "R32")
      (value "100k")
      (footprint "eagle-import:R0805")
      (libsource (lib "eagle-import") (part "R-EU_R0805"))
    )
    (comp (ref "R33")
      (value "100k")
      (footprint "eagle-import:R0805")
      (libsource (lib "eagle-import") (part "R-EU_R0805"))
    )
    (comp (ref "R34")
      (value "100k")
      (footprint "eagle-import:R0805")
      (libsource (lib "eagle-import") (part "R-EU_R0805"))
    )
    (comp (ref "R39")
      (value "100k")
      (footprint "eagle-import:R0805")
      (libsource (lib "eagle-import") (part "R-EU_R0805"))
    )
    (comp (ref "R40")
      (value "100k")
      (footprint "eagle-import:R0805")
      (libsource (lib "eagle-import") (part "R-EU_R0805"))
    )
    (comp (ref "R41")
      (value "100k")
      (footprint "eagle-import:R0805")
      (libsource (lib "eagle-import") (part "R-EU_R0805"))
    )
    (comp (ref "R42")
      (value "100k")
      (footprint "eagle-import:R0805")
      (libsource (lib "eagle-import") (part "R-EU_R0805"))
    )
    (comp (ref "SJ2") (value "SJ") (footprint "eagle-import:SJ") (libsource (lib "eagle-import") (part "SJ")))
    (comp (ref "C4")
      (value "2.2µ")
      (footprint "eagle-import:C0805")
      (libsource (lib "eagle-import") (part "C-EUC0805"))
    )
    (comp (ref "C5")
      (value "2.2µ")
      (footprint "eagle-import:C0805")
      (libsource (lib "eagle-import") (part "C-EUC0805"))
    )
    (comp (ref "C6")
      (value "100n")
      (footprint "eagle-import:C0805")
      (libsource (lib "eagle-import") (part "C-EUC0805"))
    )
    (comp (ref "C7")
      (value "10µ")
      (footprint "eagle-import:C0805")
      (libsource (lib "eagle-import") (part "C-EUC0805"))
    )
    (comp (ref "C8")
      (value "10µ")
      (footprint "eagle-import:C0805")
      (libsource (lib "eagle-import") (part "C-EUC0805"))
    )
    (comp (ref "C9")
      (value "10µ")
      (footprint "eagle-import:C0805")
      (libsource (lib "eagle-import") (part "C-EUC0805"))
    )
    (comp (ref "C10")
      (value "100n")
      (footprint "eagle-import:C0805")
      (libsource (lib "eagle-import") (part "C-EUC0805"))
    )
    (comp (ref "C11")
      (value "100n")
      (footprint "eagle-import:C0805")
      (libsource (lib "eagle-import") (part "C-EUC0805"))
    )
    (comp (ref "C12")
      (value "100n")
      (footprint "eagle-import:C0805")
      (libsource (lib "eagle-import") (part "C-EUC0805"))
    )
    (comp (ref "C13")
      (value "10µ")
      (footprint "eagle-import:C0805")
      (libsource (lib "eagle-import") (part "C-EUC0805"))
    )
    (comp (ref "C14")
      (value "10µ")
      (footprint "eagle-import:C0805")
      (libsource (lib "eagle-import") (part "C-EUC0805"))
    )
    (comp (ref "C15")
      (value "10µ")
      (footprint "eagle-import:C0805")
      (libsource (lib "eagle-import") (part "C-EUC0805"))
    )
    (comp (ref "C16")
      (value "2.2n")
      (footprint "eagle-import:C0805")
      (libsource (lib "eagle-import") (part "C-EUC0805"))
    )
    (comp (ref "C17")
      (value "2.2n")
      (footprint "eagle-import:C0805")
      (libsource (lib "eagle-import") (part "C-EUC0805"))
    )
    (comp (ref "IC1")
      (value "LP2981-33DBVR")
      (footprint "eagle-import:SOT23-5")
      (libsource (lib "eagle-import") (part "LP2981M5"))
    )
    (comp (ref "IC2")
      (value "LP2981-33DBVR")
      (footprint "eagle-import:SOT23-5")
      (libsource (lib "eagle-import") (part "LP2981M5"))
    )
    (comp (ref "R17")
      (value "470")
      (footprint "eagle-import:M0805")
      (libsource (lib "eagle-import") (part "R-EU_M0805"))
    )
    (comp (ref "R18")
      (value "470")
      (footprint "eagle-import:M0805")
      (libsource (lib "eagle-import") (part "R-EU_M0805"))
    )
    (comp (ref "U1")
      (value "PCM5102APWR")
      (footprint "eagle-import:SOP65P640X120-20N")
      (fields (field (name "MF") "Texas Instruments"))
      (libsource (lib "eagle-import") (part "PCM5102APWR"))
    )
    (comp (ref "A75")
      (value "SMD2")
      (footprint "eagle-import:SMD1,27-2,54")
      (libsource (lib "eagle-import") (part "SMD2"))
    )
    (comp (ref "APSU")
      (value "39-30-1060_BLANK")
      (footprint "eagle-import:5569_6P")
      (libsource (lib "eagle-import") (part "39-30-1060_BLANK"))
    )
    (comp (ref "C100")
      (value "FK 470/16 AP")
      (footprint "eagle-import:153CLV-0810")
      (libsource (lib "eagle-import") (part "CPOL-EU153CLV-0810"))
    )
    (comp (ref "C101")
      (value "CPOL-EU153CLV-0810")
      (footprint "eagle-import:153CLV-0810")
      (libsource (lib "eagle-import") (part "CPOL-EU153CLV-0810"))
    )
    (comp (ref "C102")
      (value "FK-V 1,0M 6,3")
      (footprint "eagle-import:153CLV-0810")
      (libsource (lib "eagle-import") (part "CPOL-EU153CLV-0810"))
    )
    (comp (ref "C103")
      (value "ECC MZL100ARA681")
      (footprint "eagle-import:153CLV-0810")
      (libsource (lib "eagle-import") (part "CPOL-EU153CLV-0810"))
    )
    (comp (ref "C104")
      (value "ECC MZL100ARA681")
      (footprint "eagle-import:153CLV-0810")
      (libsource (lib "eagle-import") (part "CPOL-EU153CLV-0810"))
    )
    (comp (ref "D33")
      (value "SMD2")
      (footprint "eagle-import:SMD1,27-2,54")
      (libsource (lib "eagle-import") (part "SMD2"))
    )
    (comp (ref "D120")
      (value "SMD2")
      (footprint "eagle-import:SMD1,27-2,54")
      (libsource (lib "eagle-import") (part "SMD2"))
    )
    (comp (ref "DPSU")
      (value "39-30-1060_BLANK")
      (footprint "eagle-import:5569_6P")
      (libsource (lib "eagle-import") (part "39-30-1060_BLANK"))
    )
    (comp (ref "EN")
      (value "SMD2")
      (footprint "eagle-import:SMD1,27-2,54")
      (libsource (lib "eagle-import") (part "SMD2"))
    )
    (comp (ref "GND")
      (value "SMD2")
      (footprint "eagle-import:SMD1,27-2,54")
      (libsource (lib "eagle-import") (part "SMD2"))
    )
    (comp (ref "H3")
      (value "MOUNT-HOLE3.3")
      (footprint "eagle-import:3,3")
      (libsource (lib "eagle-import") (part "MOUNT-HOLE3.3"))
    )
    (comp (ref "H4")
      (value "MOUNT-HOLE3.3")
      (footprint "eagle-import:3,3")
      (libsource (lib "eagle-import") (part "MOUNT-HOLE3.3"))
    )
    (comp (ref "H5")
      (value "MOUNT-HOLE3.3")
      (footprint "eagle-import:3,3")
      (libsource (lib "eagle-import") (part "MOUNT-HOLE3.3"))
    )
    (comp (ref "H6")
      (value "MOUNT-HOLE3.3")
      (footprint "eagle-import:3,3")
      (libsource (lib "eagle-import") (part "MOUNT-HOLE3.3"))
    )
    (comp (ref "SJ3") (value "SJ") (footprint "eagle-import:SJ") (libsource (lib "eagle-import") (part "SJ")))
    (comp (ref "SPK")
      (value "39-30-1060_BLANK")
      (footprint "eagle-import:5569_6P")
      (libsource (lib "eagle-import") (part "39-30-1060_BLANK"))
    )
    (comp (ref "VAMP")
      (value "SMD2")
      (footprint "eagle-import:SMD1,27-2,54")
      (libsource (lib "eagle-import") (part "SMD2"))
    )
  )
  (nets
    (net (code "1") (name "A50") (class "Default")
      (node (ref "A50") (pin "1") (pinfunction "P_1") (pintype "passive"))
      (node (ref "C33") (pin "1") (pinfunction "1_1") (pintype "passive"))
      (node (ref "C35") (pin "1") (pinfunction "1_1") (pintype "passive"))
      (node (ref "C36") (pin "1") (pinfunction "1_1") (pintype "passive"))
      (node (ref "IC3") (pin "4") (pinfunction "V+_4") (pintype "power_in"))
      (node (ref "IC4") (pin "4") (pinfunction "V+_4") (pintype "power_in"))
      (node (ref "IC5") (pin "5") (pinfunction "VOUT_5") (pintype "output"))
      (node (ref "R14") (pin "2") (pinfunction "2_2") (pintype "passive"))
      (node (ref "R33") (pin "1") (pinfunction "1_1") (pintype "passive"))
      (node (ref "R58") (pin "2") (pinfunction "2_2") (pintype "passive"))
    )
    (net (code "2") (name "A75") (class "Default")
      (node (ref "A75") (pin "1") (pinfunction "P_1") (pintype "passive"))
      (node (ref "APSU") (pin "P$4") (pinfunction "4_P$4") (pintype "bidirectional"))
      (node (ref "C103") (pin "+") (pinfunction "+_+") (pintype "passive"))
      (node (ref "C104") (pin "+") (pinfunction "+_+") (pintype "passive"))
      (node (ref "C105") (pin "1") (pinfunction "1_1") (pintype "passive"))
      (node (ref "C14") (pin "1") (pinfunction "1_1") (pintype "passive"))
      (node (ref "C15") (pin "1") (pinfunction "1_1") (pintype "passive"))
      (node (ref "C34") (pin "1") (pinfunction "1_1") (pintype "passive"))
      (node (ref "IC1") (pin "1") (pinfunction "VIN_1") (pintype "power_in"))
      (node (ref "IC1") (pin "3") (pinfunction "ON_3") (pintype "input"))
      (node (ref "IC2") (pin "1") (pinfunction "VIN_1") (pintype "power_in"))
      (node (ref "IC2") (pin "3") (pinfunction "ON_3") (pintype "input"))
      (node (ref "IC5") (pin "1") (pinfunction "VIN_1") (pintype "power_in"))
      (node (ref "IC5") (pin "3") (pinfunction "ON_3") (pintype "input"))
      (node (ref "IC6") (pin "8") (pinfunction "V+_8") (pintype "power_in"))
    )
    (net (code "3") (name "AGND") (class "Default")
      (node (ref "BT1") (pin "57") (pinfunction "AGND_57") (pintype "bidirectional"))
    )
    (net (code "4") (name "AMP_EN") (class "Default")
      (node (ref "IC7") (pin "18") (pinfunction "/RESET_18") (pintype "bidirectional"))
      (node (ref "IC8") (pin "18") (pinfunction "/RESET_18") (pintype "bidirectional"))
      (node (ref "R60") (pin "2") (pinfunction "2_2") (pintype "passive"))
      (node (ref "SJ1") (pin "2") (pinfunction "2_2") (pintype "passive"))
    )
    (net (code "5") (name "AMP_LN") (class "Default")
      (node (ref "C27") (pin "1") (pinfunction "1_1") (pintype "passive"))
      (node (ref "IC7") (pin "17") (pinfunction "INPUT_D_17") (pintype "bidirectional"))
    )
    (net (code "6") (name "AMP_LP") (class "Default")
      (node (ref "C26") (pin "1") (pinfunction "1_1") (pintype "passive"))
      (node (ref "IC7") (pin "16") (pinfunction "INPUT_C_16") (pintype "bidirectional"))
    )
    (net (code "7") (name "AMP_RN") (class "Default")
      (node (ref "C25") (pin "1") (pinfunction "1_1") (pintype "passive"))
      (node (ref "IC7") (pin "6") (pinfunction "INPUT_B_6") (pintype "bidirectional"))
    )
    (net (code "8") (name "AMP_RP") (class "Default")
      (node (ref "C24") (pin "1") (pinfunction "1_1") (pintype "passive"))
      (node (ref "IC7") (pin "5") (pinfunction "INPUT_A_5") (pintype "bidirectional"))
    )
    (net (code "9") (name "AMP_SN") (class "Default")
      (node (ref "C29") (pin "1") (pinfunction "1_1") (pintype "passive"))
      (node (ref "IC8") (pin "6") (pinfunction "INPUT_B_6") (pintype "bidirectional"))
    )
    (net (code "10") (name "AMP_SP") (class "Default")
      (node (ref "C28") (pin "1") (pinfunction "1_1") (pintype "passive"))
      (node (ref "IC8") (pin "5") (pinfunction "INPUT_A_5") (pintype "bidirectional"))
    )
    (net (code "11") (name "AUX_LN") (class "Default")
      (node (ref "BT1") (pin "55") (pinfunction "MIC_LN_55") (pintype "bidirectional"))
      (node (ref "C40") (pin "1") (pinfunction "1_1") (pintype "passive"))
    )
    (net (code "12") (name "AUX_LP") (class "Default")
      (node (ref "BT1") (pin "56") (pinfunction "MIC_LP_56") (pintype "bidirectional"))
      (node (ref "C39") (pin "1") (pinfunction "1_1") (pintype "passive"))
    )
    (net (code "13") (name "AUX_RN") (class "Default")
      (node (ref "BT1") (pin "51") (pinfunction "MIC_RN_51") (pintype "bidirectional"))
      (node (ref "C38") (pin "1") (pinfunction "1_1") (pintype "passive"))
    )
    (net (code "14") (name "AUX_RP") (class "Default")
      (node (ref "BT1") (pin "52") (pinfunction "MIC_RP_52") (pintype "bidirectional"))
      (node (ref "C37") (pin "1") (pinfunction "1_1") (pintype "passive"))
    )
    (net (code "15") (name "D33") (class "Default")
      (node (ref "BT1") (pin "41") (pinfunction "VDD_PADS_41") (pintype "bidirectional"))
      (node (ref "BT1") (pin "44") (pinfunction "VBAT_44") (pintype "bidirectional"))
      (node (ref "BT1") (pin "45") (pinfunction "VBAT_SENSE_45") (pintype "bidirectional"))
      (node (ref "C1") (pin "1") (pinfunction "1_1") (pintype "passive"))
      (node (ref "C102") (pin "+") (pinfunction "+_+") (pintype "passive"))
      (node (ref "C2") (pin "1") (pinfunction "1_1") (pintype "passive"))
      (node (ref "C3") (pin "1") (pinfunction "1_1") (pintype "passive"))
      (node (ref "D33") (pin "1") (pinfunction "P_1") (pintype "passive"))
      (node (ref "DPSU") (pin "P$5") (pinfunction "5_P$5") (pintype "bidirectional"))
      (node (ref "JP1") (pin "1") (pinfunction "1_1") (pintype "passive"))
      (node (ref "JP1") (pin "11") (pinfunction "11_11") (pintype "passive"))
      (node (ref "JP1") (pin "13") (pinfunction "13_13") (pintype "passive"))
      (node (ref "JP1") (pin "15") (pinfunction "15_15") (pintype "passive"))
      (node (ref "JP1") (pin "17") (pinfunction "17_17") (pintype "passive"))
      (node (ref "JP1") (pin "19") (pinfunction "19_19") (pintype "passive"))
      (node (ref "JP1") (pin "21") (pinfunction "21_21") (pintype "passive"))
      (node (ref "JP1") (pin "23") (pinfunction "23_23") (pintype "passive"))
      (node (ref "JP1") (pin "3") (pinfunction "3_3") (pintype "passive"))
      (node (ref "JP1") (pin "5") (pinfunction "5_5") (pintype "passive"))
      (node (ref "JP1") (pin "7") (pinfunction "7_7") (pintype "passive"))
      (node (ref "JP1") (pin "9") (pinfunction "9_9") (pintype "passive"))
      (node (ref "JP2") (pin "1") (pinfunction "1_1") (pintype "passive"))
      (node (ref "JP2") (pin "3") (pinfunction "3_3") (pintype "passive"))
      (node (ref "R13") (pin "1") (pinfunction "1_1") (pintype "passive"))
      (node (ref "R38") (pin "2") (pinfunction "2_2") (pintype "passive"))
      (node (ref "R57") (pin "2") (pinfunction "2_2") (pintype "passive"))
    )
    (net (code "16") (name "D120") (class "Default")
      (node (ref "C100") (pin "+") (pinfunction "+_+") (pintype "passive"))
      (node (ref "C86") (pin "2") (pinfunction "2_2") (pintype "passive"))
      (node (ref "C93") (pin "2") (pinfunction "2_2") (pintype "passive"))
      (node (ref "C98") (pin "+") (pinfunction "+_+") (pintype "passive"))
      (node (ref "C99") (pin "+") (pinfunction "+_+") (pintype "passive"))
      (node (ref "D120") (pin "1") (pinfunction "P_1") (pintype "passive"))
      (node (ref "DPSU") (pin "P$4") (pinfunction "4_P$4") (pintype "bidirectional"))
      (node (ref "IC7") (pin "2") (pinfunction "VDD_2") (pintype "bidirectional"))
      (node (ref "IC8") (pin "2") (pinfunction "VDD_2") (pintype "bidirectional"))
      (node (ref "R51") (pin "1") (pinfunction "1_1") (pintype "passive"))
      (node (ref "R52") (pin "1") (pinfunction "1_1") (pintype "passive"))
      (node (ref "R55") (pin "1") (pinfunction "1_1") (pintype "passive"))
      (node (ref "R56") (pin "1") (pinfunction "1_1") (pintype "passive"))
    )
    (net (code "17") (name "DETECT") (class "Default")
      (node (ref "DET") (pin "1") (pinfunction "P_1") (pintype "passive"))
      (node (ref "JP3") (pin "2") (pinfunction "2_2") (pintype "passive"))
      (node (ref "R13") (pin "2") (pinfunction "2_2") (pintype "passive"))
      (node (ref "SJ2") (pin "1") (pinfunction "1_1") (pintype "passive"))
    )
    (net (code "18") (name "EN") (class "Default")
      (node (ref "APSU") (pin "P$5") (pinfunction "5_P$5") (pintype "bidirectional"))
      (node (ref "EN") (pin "1") (pinfunction "P_1") (pintype "passive"))
      (node (ref "SJ3") (pin "2") (pinfunction "2_2") (pintype "passive"))
    )
    (net (code "19") (name "GND") (class "Default")
      (node (ref "APSU") (pin "P$1") (pinfunction "1_P$1") (pintype "bidirectional"))
      (node (ref "APSU") (pin "P$2") (pinfunction "2_P$2") (pintype "bidirectional"))
      (node (ref "APSU") (pin "P$3") (pinfunction "3_P$3") (pintype "bidirectional"))
      (node (ref "BT1") (pin "19") (pinfunction "GND_19") (pintype "bidirectional"))
      (node (ref "BT1") (pin "26") (pinfunction "GND_26") (pintype "bidirectional"))
      (node (ref "BT1") (pin "4") (pinfunction "GND_4") (pintype "bidirectional"))
      (node (ref "BT1") (pin "42") (pinfunction "GND_42") (pintype "bidirectional"))
      (node (ref "BT1") (pin "50") (pinfunction "GND_50") (pintype "bidirectional"))
      (node (ref "BT1") (pin "63") (pinfunction "GND_63") (pintype "bidirectional"))
      (node (ref "BT1") (pin "65") (pinfunction "GND_65") (pintype "bidirectional"))
      (node (ref "C1") (pin "2") (pinfunction "2_2") (pintype "passive"))
      (node (ref "C10") (pin "2") (pinfunction "2_2") (pintype "passive"))
      (node (ref "C100") (pin "-") (pinfunction "-_-") (pintype "passive"))
      (node (ref "C101") (pin "-") (pinfunction "-_-") (pintype "passive"))
      (node (ref "C102") (pin "-") (pinfunction "-_-") (pintype "passive"))
      (node (ref "C103") (pin "-") (pinfunction "-_-") (pintype "passive"))
      (node (ref "C104") (pin "-") (pinfunction "-_-") (pintype "passive"))
      (node (ref "C105") (pin "2") (pinfunction "2_2") (pintype "passive"))
      (node (ref "C11") (pin "2") (pinfunction "2_2") (pintype "passive"))
      (node (ref "C12") (pin "2") (pinfunction "2_2") (pintype "passive"))
      (node (ref "C13") (pin "2") (pinfunction "2_2") (pintype "passive"))
      (node (ref "C14") (pin "2") (pinfunction "2_2") (pintype "passive"))
      (node (ref "C15") (pin "2") (pinfunction "2_2") (pintype "passive"))
      (node (ref "C16") (pin "2") (pinfunction "2_2") (pintype "passive"))
      (node (ref "C17") (pin "2") (pinfunction "2_2") (pintype "passive"))
      (node (ref "C18") (pin "2") (pinfunction "2_2") (pintype "passive"))
      (node (ref "C19") (pin "2") (pinfunction "2_2") (pintype "passive"))
      (node (ref "C2") (pin "2") (pinfunction "2_2") (pintype "passive"))
      (node (ref "C20") (pin "2") (pinfunction "2_2") (pintype "passive"))
      (node (ref "C21") (pin "2") (pinfunction "2_2") (pintype "passive"))
      (node (ref "C22") (pin "2") (pinfunction "2_2") (pintype "passive"))
      (node (ref "C23") (pin "2") (pinfunction "2_2") (pintype "passive"))
      (node (ref "C3") (pin "2") (pinfunction "2_2") (pintype "passive"))
      (node (ref "C32") (pin "2") (pinfunction "2_2") (pintype "passive"))
      (node (ref "C33") (pin "2") (pinfunction "2_2") (pintype "passive"))
      (node (ref "C34") (pin "2") (pinfunction "2_2") (pintype "passive"))
      (node (ref "C35") (pin "2") (pinfunction "2_2") (pintype "passive"))
      (node (ref "C36") (pin "2") (pinfunction "2_2") (pintype "passive"))
      (node (ref "C42") (pin "2") (pinfunction "2_2") (pintype "passive"))
      (node (ref "C43") (pin "2") (pinfunction "2_2") (pintype "passive"))
      (node (ref "C44") (pin "2") (pinfunction "2_2") (pintype "passive"))
      (node (ref "C45") (pin "2") (pinfunction "2_2") (pintype "passive"))
      (node (ref "C46") (pin "2") (pinfunction "2_2") (pintype "passive"))
      (node (ref "C47") (pin "1") (pinfunction "1_1") (pintype "passive"))
      (node (ref "C48") (pin "2") (pinfunction "2_2") (pintype "passive"))
      (node (ref "C49") (pin "1") (pinfunction "1_1") (pintype "passive"))
      (node (ref "C5") (pin "2") (pinfunction "2_2") (pintype "passive"))
      (node (ref "C50") (pin "2") (pinfunction "2_2") (pintype "passive"))
      (node (ref "C51") (pin "1") (pinfunction "1_1") (pintype "passive"))
      (node (ref "C52") (pin "2") (pinfunction "2_2") (pintype "passive"))
      (node (ref "C53") (pin "1") (pinfunction "1_1") (pintype "passive"))
      (node (ref "C54") (pin "2") (pinfunction "2_2") (pintype "passive"))
      (node (ref "C55") (pin "1") (pinfunction "1_1") (pintype "passive"))
      (node (ref "C56") (pin "2") (pinfunction "2_2") (pintype "passive"))
      (node (ref "C57") (pin "1") (pinfunction "1_1") (pintype "passive"))
      (node (ref "C6") (pin "2") (pinfunction "2_2") (pintype "passive"))
      (node (ref "C64") (pin "2") (pinfunction "2_2") (pintype "passive"))
      (node (ref "C65") (pin "2") (pinfunction "2_2") (pintype "passive"))
      (node (ref "C66") (pin "2") (pinfunction "2_2") (pintype "passive"))
      (node (ref "C67") (pin "2") (pinfunction "2_2") (pintype "passive"))
      (node (ref "C68") (pin "1") (pinfunction "1_1") (pintype "passive"))
      (node (ref "C69") (pin "1") (pinfunction "1_1") (pintype "passive"))
      (node (ref "C7") (pin "2") (pinfunction "2_2") (pintype "passive"))
      (node (ref "C70") (pin "1") (pinfunction "1_1") (pintype "passive"))
      (node (ref "C71") (pin "2") (pinfunction "2_2") (pintype "passive"))
      (node (ref "C72") (pin "-") (pinfunction "-_-") (pintype "passive"))
      (node (ref "C73") (pin "-") (pinfunction "-_-") (pintype "passive"))
      (node (ref "C74") (pin "-") (pinfunction "-_-") (pintype "passive"))
      (node (ref "C75") (pin "-") (pinfunction "-_-") (pintype "passive"))
      (node (ref "C8") (pin "2") (pinfunction "2_2") (pintype "passive"))
      (node (ref "C84") (pin "1") (pinfunction "1_1") (pintype "passive"))
      (node (ref "C85") (pin "1") (pinfunction "1_1") (pintype "passive"))
      (node (ref "C86") (pin "1") (pinfunction "1_1") (pintype "passive"))
      (node (ref "C87") (pin "1") (pinfunction "1_1") (pintype "passive"))
      (node (ref "C88") (pin "1") (pinfunction "1_1") (pintype "passive"))
      (node (ref "C89") (pin "1") (pinfunction "1_1") (pintype "passive"))
      (node (ref "C9") (pin "2") (pinfunction "2_2") (pintype "passive"))
      (node (ref "C90") (pin "2") (pinfunction "2_2") (pintype "passive"))
      (node (ref "C91") (pin "1") (pinfunction "1_1") (pintype "passive"))
      (node (ref "C92") (pin "1") (pinfunction "1_1") (pintype "passive"))
      (node (ref "C93") (pin "1") (pinfunction "1_1") (pintype "passive"))
      (node (ref "C94") (pin "2") (pinfunction "2_2") (pintype "passive"))
      (node (ref "C95") (pin "2") (pinfunction "2_2") (pintype "passive"))
      (node (ref "C96") (pin "2") (pinfunction "2_2") (pintype "passive"))
      (node (ref "C97") (pin "2") (pinfunction "2_2") (pintype "passive"))
      (node (ref "C98") (pin "-") (pinfunction "-_-") (pintype "passive"))
      (node (ref "C99") (pin "-") (pinfunction "-_-") (pintype "passive"))
      (node (ref "DPSU") (pin "P$1") (pinfunction "1_P$1") (pintype "bidirectional"))
      (node (ref "DPSU") (pin "P$2") (pinfunction "2_P$2") (pintype "bidirectional"))
      (node (ref "DPSU") (pin "P$3") (pinfunction "3_P$3") (pintype "bidirectional"))
      (node (ref "GND") (pin "1") (pinfunction "P_1") (pintype "passive"))
      (node (ref "IC1") (pin "2") (pinfunction "GND_2") (pintype "power_in"))
      (node (ref "IC2") (pin "2") (pinfunction "GND_2") (pintype "power_in"))
      (node (ref "IC3") (pin "11") (pinfunction "V-_11") (pintype "power_in"))
      (node (ref "IC4") (pin "11") (pinfunction "V-_11") (pintype "power_in"))
      (node (ref "IC5") (pin "2") (pinfunction "GND_2") (pintype "power_in"))
      (node (ref "IC6") (pin "4") (pinfunction "V-_4") (pintype "power_in"))
      (node (ref "IC7") (pin "12") (pinfunction "GND/1_12") (pintype "bidirectional"))
      (node (ref "IC7") (pin "13") (pinfunction "GND/2_13") (pintype "bidirectional"))
      (node (ref "IC7") (pin "25") (pinfunction "GND/3_25") (pintype "bidirectional"))
      (node (ref "IC7") (pin "26") (pinfunction "GND/4_26") (pintype "bidirectional"))
      (node (ref "IC7") (pin "3") (pinfunction "M1_3") (pintype "bidirectional"))
      (node (ref "IC7") (pin "33") (pinfunction "GND/5_33") (pintype "bidirectional"))
      (node (ref "IC7") (pin "34") (pinfunction "GND/6_34") (pintype "bidirectional"))
      (node (ref "IC7") (pin "4") (pinfunction "M2_4") (pintype "bidirectional"))
      (node (ref "IC7") (pin "41") (pinfunction "GND/7_41") (pintype "bidirectional"))
      (node (ref "IC7") (pin "42") (pinfunction "GND/8_42") (pintype "bidirectional"))
      (node (ref "IC8") (pin "12") (pinfunction "GND/1_12") (pintype "bidirectional"))
      (node (ref "IC8") (pin "13") (pinfunction "GND/2_13") (pintype "bidirectional"))
      (node (ref "IC8") (pin "16") (pinfunction "INPUT_C_16") (pintype "bidirectional"))
      (node (ref "IC8") (pin "17") (pinfunction "INPUT_D_17") (pintype "bidirectional"))
      (node (ref "IC8") (pin "25") (pinfunction "GND/3_25") (pintype "bidirectional"))
      (node (ref "IC8") (pin "26") (pinfunction "GND/4_26") (pintype "bidirectional"))
      (node (ref "IC8") (pin "3") (pinfunction "M1_3") (pintype "bidirectional"))
      (node (ref "IC8") (pin "33") (pinfunction "GND/5_33") (pintype "bidirectional"))
      (node (ref "IC8") (pin "34") (pinfunction "GND/6_34") (pintype "bidirectional"))
      (node (ref "IC8") (pin "41") (pinfunction "GND/7_41") (pintype "bidirectional"))
      (node (ref "IC8") (pin "42") (pinfunction "GND/8_42") (pintype "bidirectional"))
      (node (ref "J1") (pin "GND@0") (pinfunction "2_GND@0") (pintype "passive"))
      (node (ref "JP2") (pin "2") (pinfunction "2_2") (pintype "passive"))
      (node (ref "JP3") (pin "1") (pinfunction "1_1") (pintype "passive"))
      (node (ref "JP3") (pin "3") (pinfunction "3_3") (pintype "passive"))
      (node (ref "JP3") (pin "5") (pinfunction "5_5") (pintype "passive"))
      (node (ref "JP3") (pin "7") (pinfunction "7_7") (pintype "passive"))
      (node (ref "JP3") (pin "9") (pinfunction "9_9") (pintype "passive"))
      (node (ref "R34") (pin "2") (pinfunction "2_2") (pintype "passive"))
      (node (ref "R37") (pin "2") (pinfunction "2_2") (pintype "passive"))
      (node (ref "R39") (pin "2") (pinfunction "2_2") (pintype "passive"))
      (node (ref "R40") (pin "2") (pinfunction "2_2") (pintype "passive"))
      (node (ref "R41") (pin "2") (pinfunction "2_2") (pintype "passive"))
      (node (ref "R42") (pin "2") (pinfunction "2_2") (pintype "passive"))
      (node (ref "R43") (pin "1") (pinfunction "1_1") (pintype "passive"))
      (node (ref "R44") (pin "1") (pinfunction "1_1") (pintype "passive"))
      (node (ref "R45") (pin "1") (pinfunction "1_1") (pintype "passive"))
      (node (ref "R46") (pin "1") (pinfunction "1_1") (pintype "passive"))
      (node (ref "R47") (pin "1") (pinfunction "1_1") (pintype "passive"))
      (node (ref "R48") (pin "1") (pinfunction "1_1") (pintype "passive"))
      (node (ref "R49") (pin "1") (pinfunction "1_1") (pintype "passive"))
      (node (ref "R50") (pin "1") (pinfunction "1_1") (pintype "passive"))
      (node (ref "R53") (pin "1") (pinfunction "1_1") (pintype "passive"))
      (node (ref "R54") (pin "1") (pinfunction "1_1") (pintype "passive"))
      (node (ref "R59") (pin "1") (pinfunction "1_1") (pintype "passive"))
      (node (ref "R60") (pin "1") (pinfunction "1_1") (pintype "passive"))
      (node (ref "T1") (pin "2") (pinfunction "S_2") (pintype "passive"))
      (node (ref "T2") (pin "2") (pinfunction "S_2") (pintype "passive"))
      (node (ref "U1") (pin "10") (pinfunction "DEMP_10") (pintype "input"))
      (node (ref "U1") (pin "11") (pinfunction "FLT_11") (pintype "input"))
      (node (ref "U1") (pin "12") (pinfunction "SCK_12") (pintype "input"))
      (node (ref "U1") (pin "19") (pinfunction "DGND_19") (pintype "power_in"))
      (node (ref "U1") (pin "3") (pinfunction "CPGND_3") (pintype "power_in"))
      (node (ref "U1") (pin "9") (pinfunction "AGND_9") (pintype "power_in"))
    )
    (net (code "20") (name "LED0") (class "Default")
      (node (ref "BT1") (pin "20") (pinfunction "LED0_20") (pintype "bidirectional"))
      (node (ref "R1") (pin "2") (pinfunction "2_2") (pintype "passive"))
    )
    (net (code "21") (name "LED1") (class "Default")
      (node (ref "BT1") (pin "21") (pinfunction "LED1_21") (pintype "bidirectional"))
      (node (ref "R2") (pin "2") (pinfunction "2_2") (pintype "passive"))
    )
    (net (code "22") (name "LED2") (class "Default")
      (node (ref "BT1") (pin "22") (pinfunction "LED2_22") (pintype "bidirectional"))
      (node (ref "R3") (pin "2") (pinfunction "2_2") (pintype "passive"))
    )
    (net (code "23") (name "LINE_LN") (class "Default")
      (node (ref "C40") (pin "2") (pinfunction "2_2") (pintype "passive"))
      (node (ref "JP3") (pin "10") (pinfunction "10_10") (pintype "passive"))
      (node (ref "R42") (pin "1") (pinfunction "1_1") (pintype "passive"))
    )
    (net (code "24") (name "LINE_LP") (class "Default")
      (node (ref "C39") (pin "2") (pinfunction "2_2") (pintype "passive"))
      (node (ref "JP3") (pin "8") (pinfunction "8_8") (pintype "passive"))
      (node (ref "R41") (pin "1") (pinfunction "1_1") (pintype "passive"))
    )
    (net (code "25") (name "LINE_RN") (class "Default")
      (node (ref "C38") (pin "2") (pinfunction "2_2") (pintype "passive"))
      (node (ref "JP3") (pin "6") (pinfunction "6_6") (pintype "passive"))
      (node (ref "R40") (pin "1") (pinfunction "1_1") (pintype "passive"))
    )
    (net (code "26") (name "LINE_RP") (class "Default")
      (node (ref "C37") (pin "2") (pinfunction "2_2") (pintype "passive"))
      (node (ref "JP3") (pin "4") (pinfunction "4_4") (pintype "passive"))
      (node (ref "R39") (pin "1") (pinfunction "1_1") (pintype "passive"))
    )
    (net (code "27") (name "LN") (class "Default")
      (node (ref "C49") (pin "2") (pinfunction "2_2") (pintype "passive"))
      (node (ref "C55") (pin "2") (pinfunction "2_2") (pintype "passive"))
      (node (ref "C61") (pin "2") (pinfunction "2_2") (pintype "passive"))
      (node (ref "L2") (pin "4") (pinfunction "L2_2_4") (pintype "bidirectional"))
      (node (ref "SPK") (pin "P$2") (pinfunction "2_P$2") (pintype "bidirectional"))
    )
    (net (code "28") (name "LP") (class "Default")
      (node (ref "C48") (pin "1") (pinfunction "1_1") (pintype "passive"))
      (node (ref "C54") (pin "1") (pinfunction "1_1") (pintype "passive"))
      (node (ref "C60") (pin "1") (pinfunction "1_1") (pintype "passive"))
      (node (ref "L2") (pin "1") (pinfunction "L1_1_1") (pintype "bidirectional"))
      (node (ref "SPK") (pin "P$5") (pinfunction "5_P$5") (pintype "bidirectional"))
    )
    (net (code "29") (name "LVL") (class "Default")
      (node (ref "APSU") (pin "P$6") (pinfunction "6_P$6") (pintype "bidirectional"))
      (node (ref "R57") (pin "1") (pinfunction "1_1") (pintype "passive"))
      (node (ref "T2") (pin "3") (pinfunction "D_3") (pintype "passive"))
    )
    (net (code "30") (name "Net-(BT1-RF_IN)") (class "Default")
      (node (ref "BT1") (pin "64") (pinfunction "RF_IN_64") (pintype "bidirectional"))
      (node (ref "J1") (pin "S") (pinfunction "1_S") (pintype "passive"))
    )
    (net (code "31") (name "Net-(C18-Pad1)") (class "Default")
      (node (ref "C18") (pin "1") (pinfunction "1_1") (pintype "passive"))
      (node (ref "R25") (pin "1") (pinfunction "1_1") (pintype "passive"))
    )
    (net (code "32") (name "Net-(C19-Pad1)") (class "Default")
      (node (ref "C19") (pin "1") (pinfunction "1_1") (pintype "passive"))
      (node (ref "R26") (pin "1") (pinfunction "1_1") (pintype "passive"))
    )
    (net (code "33") (name "Net-(C20-Pad1)") (class "Default")
      (node (ref "C20") (pin "1") (pinfunction "1_1") (pintype "passive"))
      (node (ref "R27") (pin "1") (pinfunction "1_1") (pintype "passive"))
    )
    (net (code "34") (name "Net-(C21-Pad1)") (class "Default")
      (node (ref "C21") (pin "1") (pinfunction "1_1") (pintype "passive"))
      (node (ref "R28") (pin "1") (pinfunction "1_1") (pintype "passive"))
    )
    (net (code "35") (name "Net-(C22-Pad1)") (class "Default")
      (node (ref "C22") (pin "1") (pinfunction "1_1") (pintype "passive"))
      (node (ref "R29") (pin "1") (pinfunction "1_1") (pintype "passive"))
    )
    (net (code "36") (name "Net-(C23-Pad1)") (class "Default")
      (node (ref "C23") (pin "1") (pinfunction "1_1") (pintype "passive"))
      (node (ref "R30") (pin "1") (pinfunction "1_1") (pintype "passive"))
    )
    (net (code "37") (name "Net-(C42-Pad1)") (class "Default")
      (node (ref "C42") (pin "1") (pinfunction "1_1") (pintype "passive"))
      (node (ref "R16") (pin "2") (pinfunction "2_2") (pintype "passive"))
    )
    (net (code "38") (name "Net-(C58-Pad2)") (class "Default")
      (node (ref "C58") (pin "2") (pinfunction "2_2") (pintype "passive"))
      (node (ref "R43") (pin "2") (pinfunction "2_2") (pintype "passive"))
    )
    (net (code "39") (name "Net-(C59-Pad1)") (class "Default")
      (node (ref "C59") (pin "1") (pinfunction "1_1") (pintype "passive"))
      (node (ref "R44") (pin "2") (pinfunction "2_2") (pintype "passive"))
    )
    (net (code "40") (name "Net-(C60-Pad2)") (class "Default")
      (node (ref "C60") (pin "2") (pinfunction "2_2") (pintype "passive"))
      (node (ref "R45") (pin "2") (pinfunction "2_2") (pintype "passive"))
    )
    (net (code "41") (name "Net-(C61-Pad1)") (class "Default")
      (node (ref "C61") (pin "1") (pinfunction "1_1") (pintype "passive"))
      (node (ref "R46") (pin "2") (pinfunction "2_2") (pintype "passive"))
    )
    (net (code "42") (name "Net-(C62-Pad2)") (class "Default")
      (node (ref "C62") (pin "2") (pinfunction "2_2") (pintype "passive"))
      (node (ref "R47") (pin "2") (pinfunction "2_2") (pintype "passive"))
    )
    (net (code "43") (name "Net-(C63-Pad1)") (class "Default")
      (node (ref "C63") (pin "1") (pinfunction "1_1") (pintype "passive"))
      (node (ref "R48") (pin "2") (pinfunction "2_2") (pintype "passive"))
    )
    (net (code "44") (name "Net-(D1-PadA)") (class "Default")
      (node (ref "D1") (pin "A") (pinfunction "A_A") (pintype "passive"))
      (node (ref "R35") (pin "1") (pinfunction "1_1") (pintype "passive"))
    )
    (net (code "45") (name "Net-(IC1-VOUT)") (class "Default")
      (node (ref "C11") (pin "1") (pinfunction "1_1") (pintype "passive"))
      (node (ref "C6") (pin "1") (pinfunction "1_1") (pintype "passive"))
      (node (ref "C7") (pin "1") (pinfunction "1_1") (pintype "passive"))
      (node (ref "C8") (pin "1") (pinfunction "1_1") (pintype "passive"))
      (node (ref "IC1") (pin "5") (pinfunction "VOUT_5") (pintype "output"))
      (node (ref "U1") (pin "1") (pinfunction "CPVDD_1") (pintype "power_in"))
      (node (ref "U1") (pin "8") (pinfunction "AVDD_8") (pintype "power_in"))
    )
    (net (code "46") (name "Net-(IC2-VOUT)") (class "Default")
      (node (ref "C12") (pin "1") (pinfunction "1_1") (pintype "passive"))
      (node (ref "C13") (pin "1") (pinfunction "1_1") (pintype "passive"))
      (node (ref "IC2") (pin "5") (pinfunction "VOUT_5") (pintype "output"))
      (node (ref "U1") (pin "16") (pinfunction "FMT_16") (pintype "input"))
      (node (ref "U1") (pin "20") (pinfunction "DVDD_20") (pintype "power_in"))
    )
    (net (code "47") (name "Net-(IC3A--IN)") (class "Default")
      (node (ref "IC3") (pin "2") (pinfunction "-IN_2") (pintype "input"))
      (node (ref "R19") (pin "1") (pinfunction "1_1") (pintype "passive"))
      (node (ref "R25") (pin "2") (pinfunction "2_2") (pintype "passive"))
    )
    (net (code "48") (name "Net-(IC3A-OUT)") (class "Default")
      (node (ref "C24") (pin "2") (pinfunction "2_2") (pintype "passive"))
      (node (ref "IC3") (pin "1") (pinfunction "OUT_1") (pintype "output"))
      (node (ref "R19") (pin "2") (pinfunction "2_2") (pintype "passive"))
    )
    (net (code "49") (name "Net-(IC3B--IN)") (class "Default")
      (node (ref "IC3") (pin "6") (pinfunction "-IN_6") (pintype "input"))
      (node (ref "R20") (pin "1") (pinfunction "1_1") (pintype "passive"))
      (node (ref "R26") (pin "2") (pinfunction "2_2") (pintype "passive"))
    )
    (net (code "50") (name "Net-(IC3B-OUT)") (class "Default")
      (node (ref "C25") (pin "2") (pinfunction "2_2") (pintype "passive"))
      (node (ref "IC3") (pin "7") (pinfunction "OUT_7") (pintype "output"))
      (node (ref "R20") (pin "2") (pinfunction "2_2") (pintype "passive"))
    )
    (net (code "51") (name "Net-(IC3C--IN)") (class "Default")
      (node (ref "IC3") (pin "9") (pinfunction "-IN_9") (pintype "input"))
      (node (ref "R21") (pin "1") (pinfunction "1_1") (pintype "passive"))
      (node (ref "R27") (pin "2") (pinfunction "2_2") (pintype "passive"))
    )
    (net (code "52") (name "Net-(IC3C-OUT)") (class "Default")
      (node (ref "C26") (pin "2") (pinfunction "2_2") (pintype "passive"))
      (node (ref "IC3") (pin "8") (pinfunction "OUT_8") (pintype "output"))
      (node (ref "R21") (pin "2") (pinfunction "2_2") (pintype "passive"))
    )
    (net (code "53") (name "Net-(IC3D--IN)") (class "Default")
      (node (ref "IC3") (pin "13") (pinfunction "-IN_13") (pintype "input"))
      (node (ref "R22") (pin "1") (pinfunction "1_1") (pintype "passive"))
      (node (ref "R28") (pin "2") (pinfunction "2_2") (pintype "passive"))
    )
    (net (code "54") (name "Net-(IC3D-OUT)") (class "Default")
      (node (ref "C27") (pin "2") (pinfunction "2_2") (pintype "passive"))
      (node (ref "IC3") (pin "14") (pinfunction "OUT_14") (pintype "output"))
      (node (ref "R22") (pin "2") (pinfunction "2_2") (pintype "passive"))
    )
    (net (code "55") (name "Net-(IC4A-+IN)") (class "Default")
      (node (ref "C31") (pin "1") (pinfunction "1_1") (pintype "passive"))
      (node (ref "IC4") (pin "3") (pinfunction "+IN_3") (pintype "input"))
      (node (ref "R31") (pin "2") (pinfunction "2_2") (pintype "passive"))
    )
    (net (code "56") (name "Net-(IC4A--IN)") (class "Default")
      (node (ref "IC4") (pin "2") (pinfunction "-IN_2") (pintype "input"))
      (node (ref "R24") (pin "1") (pinfunction "1_1") (pintype "passive"))
      (node (ref "R30") (pin "2") (pinfunction "2_2") (pintype "passive"))
    )
    (net (code "57") (name "Net-(IC4A-OUT)") (class "Default")
      (node (ref "C28") (pin "2") (pinfunction "2_2") (pintype "passive"))
      (node (ref "IC4") (pin "1") (pinfunction "OUT_1") (pintype "output"))
      (node (ref "R24") (pin "2") (pinfunction "2_2") (pintype "passive"))
    )
    (net (code "58") (name "Net-(IC4B-+IN)") (class "Default")
      (node (ref "C30") (pin "1") (pinfunction "1_1") (pintype "passive"))
      (node (ref "IC4") (pin "5") (pinfunction "+IN_5") (pintype "input"))
      (node (ref "R32") (pin "2") (pinfunction "2_2") (pintype "passive"))
    )
    (net (code "59") (name "Net-(IC4B--IN)") (class "Default")
      (node (ref "IC4") (pin "6") (pinfunction "-IN_6") (pintype "input"))
      (node (ref "R23") (pin "1") (pinfunction "1_1") (pintype "passive"))
      (node (ref "R29") (pin "2") (pinfunction "2_2") (pintype "passive"))
    )
    (net (code "60") (name "Net-(IC4B-OUT)") (class "Default")
      (node (ref "C29") (pin "2") (pinfunction "2_2") (pintype "passive"))
      (node (ref "IC4") (pin "7") (pinfunction "OUT_7") (pintype "output"))
      (node (ref "R23") (pin "2") (pinfunction "2_2") (pintype "passive"))
    )
    (net (code "61") (name "Net-(IC4C-+IN)") (class "Default")
      (node (ref "C32") (pin "1") (pinfunction "1_1") (pintype "passive"))
      (node (ref "IC4") (pin "10") (pinfunction "+IN_10") (pintype "input"))
      (node (ref "R33") (pin "2") (pinfunction "2_2") (pintype "passive"))
      (node (ref "R34") (pin "1") (pinfunction "1_1") (pintype "passive"))
    )
    (net (code "62") (name "Net-(IC4C--IN)") (class "Default")
      (node (ref "IC4") (pin "8") (pinfunction "OUT_8") (pintype "output"))
      (node (ref "IC4") (pin "9") (pinfunction "-IN_9") (pintype "input"))
      (node (ref "R31") (pin "1") (pinfunction "1_1") (pintype "passive"))
      (node (ref "R32") (pin "1") (pinfunction "1_1") (pintype "passive"))
    )
    (net (code "63") (name "Net-(IC6A-+IN)") (class "Default")
      (node (ref "C41") (pin "2") (pinfunction "2_2") (pintype "passive"))
      (node (ref "IC6") (pin "3") (pinfunction "+IN_3") (pintype "input"))
      (node (ref "R14") (pin "1") (pinfunction "1_1") (pintype "passive"))
    )
    (net (code "64") (name "Net-(IC6A--IN)") (class "Default")
      (node (ref "IC6") (pin "2") (pinfunction "-IN_2") (pintype "input"))
      (node (ref "R15") (pin "2") (pinfunction "2_2") (pintype "passive"))
      (node (ref "R16") (pin "1") (pinfunction "1_1") (pintype "passive"))
    )
    (net (code "65") (name "Net-(IC6A-OUT)") (class "Default")
      (node (ref "IC6") (pin "1") (pinfunction "OUT_1") (pintype "output"))
      (node (ref "IC6") (pin "6") (pinfunction "-IN_6") (pintype "input"))
      (node (ref "R15") (pin "1") (pinfunction "1_1") (pintype "passive"))
    )
    (net (code "66") (name "Net-(IC6B-+IN)") (class "Default")
      (node (ref "IC6") (pin "5") (pinfunction "+IN_5") (pintype "input"))
      (node (ref "R36") (pin "2") (pinfunction "S_2") (pintype "passive"))
      (node (ref "R36") (pin "3") (pinfunction "A_3") (pintype "passive"))
      (node (ref "R59") (pin "2") (pinfunction "2_2") (pintype "passive"))
    )
    (net (code "67") (name "Net-(IC6B-OUT)") (class "Default")
      (node (ref "IC6") (pin "7") (pinfunction "OUT_7") (pintype "output"))
      (node (ref "R35") (pin "2") (pinfunction "2_2") (pintype "passive"))
    )
    (net (code "68") (name "Net-(IC7-AVDD)") (class "Default")
      (node (ref "C88") (pin "2") (pinfunction "2_2") (pintype "passive"))
      (node (ref "IC7") (pin "14") (pinfunction "AVDD_14") (pintype "bidirectional"))
    )
    (net (code "69") (name "Net-(IC7-BST_A)") (class "Default")
      (node (ref "C79") (pin "2") (pinfunction "2_2") (pintype "passive"))
      (node (ref "IC7") (pin "44") (pinfunction "BST_A_44") (pintype "bidirectional"))
    )
    (net (code "70") (name "Net-(IC7-BST_B)") (class "Default")
      (node (ref "C78") (pin "2") (pinfunction "2_2") (pintype "passive"))
      (node (ref "IC7") (pin "43") (pinfunction "BST_B_43") (pintype "bidirectional"))
    )
    (net (code "71") (name "Net-(IC7-BST_C)") (class "Default")
      (node (ref "C76") (pin "1") (pinfunction "1_1") (pintype "passive"))
      (node (ref "IC7") (pin "24") (pinfunction "BST_C_24") (pintype "bidirectional"))
    )
    (net (code "72") (name "Net-(IC7-BST_D)") (class "Default")
      (node (ref "C77") (pin "1") (pinfunction "1_1") (pintype "passive"))
      (node (ref "IC7") (pin "23") (pinfunction "BST_D_23") (pintype "bidirectional"))
    )
    (net (code "73") (name "Net-(IC7-C_START)") (class "Default")
      (node (ref "C89") (pin "2") (pinfunction "2_2") (pintype "passive"))
      (node (ref "IC7") (pin "15") (pinfunction "C_START_15") (pintype "bidirectional"))
    )
    (net (code "74") (name "Net-(IC7-DVDD)") (class "Default")
      (node (ref "C90") (pin "1") (pinfunction "1_1") (pintype "passive"))
      (node (ref "IC7") (pin "11") (pinfunction "DVDD_11") (pintype "bidirectional"))
    )
    (net (code "75") (name "Net-(IC7-FREQ_ADJ)") (class "Default")
      (node (ref "IC7") (pin "8") (pinfunction "FREQ_ADJ_8") (pintype "bidirectional"))
      (node (ref "R53") (pin "2") (pinfunction "2_2") (pintype "passive"))
    )
    (net (code "76") (name "Net-(IC7-GVDD_AB)") (class "Default")
      (node (ref "C92") (pin "2") (pinfunction "2_2") (pintype "passive"))
      (node (ref "IC7") (pin "1") (pinfunction "GVDD_AB_1") (pintype "bidirectional"))
      (node (ref "R56") (pin "2") (pinfunction "2_2") (pintype "passive"))
    )
    (net (code "77") (name "Net-(IC7-GVDD_CD)") (class "Default")
      (node (ref "C91") (pin "2") (pinfunction "2_2") (pintype "passive"))
      (node (ref "IC7") (pin "22") (pinfunction "GVDD_CD_22") (pintype "bidirectional"))
      (node (ref "R55") (pin "2") (pinfunction "2_2") (pintype "passive"))
    )
    (net (code "78") (name "Net-(IC7-OC_ADJ)") (class "Default")
      (node (ref "IC7") (pin "7") (pinfunction "OC_ADJ_7") (pintype "bidirectional"))
      (node (ref "R54") (pin "2") (pinfunction "2_2") (pintype "passive"))
    )
    (net (code "79") (name "Net-(IC7-OUT_A{slash}1)") (class "Default")
      (node (ref "C79") (pin "1") (pinfunction "1_1") (pintype "passive"))
      (node (ref "IC7") (pin "39") (pinfunction "OUT_A/1_39") (pintype "bidirectional"))
      (node (ref "IC7") (pin "40") (pinfunction "OUT_A/2_40") (pintype "bidirectional"))
      (node (ref "L1") (pin "3") (pinfunction "L2_1_3") (pintype "bidirectional"))
    )
    (net (code "80") (name "Net-(IC7-OUT_B)") (class "Default")
      (node (ref "C78") (pin "1") (pinfunction "1_1") (pintype "passive"))
      (node (ref "IC7") (pin "35") (pinfunction "OUT_B_35") (pintype "bidirectional"))
      (node (ref "L1") (pin "2") (pinfunction "L1_2_2") (pintype "bidirectional"))
    )
    (net (code "81") (name "Net-(IC7-OUT_C)") (class "Default")
      (node (ref "C76") (pin "2") (pinfunction "2_2") (pintype "passive"))
      (node (ref "IC7") (pin "32") (pinfunction "OUT_C_32") (pintype "bidirectional"))
      (node (ref "L2") (pin "3") (pinfunction "L2_1_3") (pintype "bidirectional"))
    )
    (net (code "82") (name "Net-(IC7-OUT_D2)") (class "Default")
      (node (ref "C77") (pin "2") (pinfunction "2_2") (pintype "passive"))
      (node (ref "IC7") (pin "27") (pinfunction "OUT_D/1_27") (pintype "bidirectional"))
      (node (ref "IC7") (pin "28") (pinfunction "OUT_D2_28") (pintype "bidirectional"))
      (node (ref "L2") (pin "2") (pinfunction "L1_2_2") (pintype "bidirectional"))
    )
    (net (code "83") (name "Net-(IC7-VBG)") (class "Default")
      (node (ref "C87") (pin "2") (pinfunction "2_2") (pintype "passive"))
      (node (ref "IC7") (pin "20") (pinfunction "VBG_20") (pintype "bidirectional"))
    )
    (net (code "84") (name "Net-(IC8-AVDD)") (class "Default")
      (node (ref "C69") (pin "2") (pinfunction "2_2") (pintype "passive"))
      (node (ref "IC8") (pin "14") (pinfunction "AVDD_14") (pintype "bidirectional"))
    )
    (net (code "85") (name "Net-(IC8-BST_A)") (class "Default")
      (node (ref "C83") (pin "2") (pinfunction "2_2") (pintype "passive"))
      (node (ref "IC8") (pin "44") (pinfunction "BST_A_44") (pintype "bidirectional"))
    )
    (net (code "86") (name "Net-(IC8-BST_B)") (class "Default")
      (node (ref "C81") (pin "2") (pinfunction "2_2") (pintype "passive"))
      (node (ref "IC8") (pin "43") (pinfunction "BST_B_43") (pintype "bidirectional"))
    )
    (net (code "87") (name "Net-(IC8-BST_C)") (class "Default")
      (node (ref "C82") (pin "1") (pinfunction "1_1") (pintype "passive"))
      (node (ref "IC8") (pin "24") (pinfunction "BST_C_24") (pintype "bidirectional"))
    )
    (net (code "88") (name "Net-(IC8-BST_D)") (class "Default")
      (node (ref "C80") (pin "1") (pinfunction "1_1") (pintype "passive"))
      (node (ref "IC8") (pin "23") (pinfunction "BST_D_23") (pintype "bidirectional"))
    )
    (net (code "89") (name "Net-(IC8-C_START)") (class "Default")
      (node (ref "C70") (pin "2") (pinfunction "2_2") (pintype "passive"))
      (node (ref "IC8") (pin "15") (pinfunction "C_START_15") (pintype "bidirectional"))
    )
    (net (code "90") (name "Net-(IC8-DVDD)") (class "Default")
      (node (ref "C71") (pin "1") (pinfunction "1_1") (pintype "passive"))
      (node (ref "IC8") (pin "11") (pinfunction "DVDD_11") (pintype "bidirectional"))
      (node (ref "IC8") (pin "4") (pinfunction "M2_4") (pintype "bidirectional"))
    )
    (net (code "91") (name "Net-(IC8-FREQ_ADJ)") (class "Default")
      (node (ref "IC8") (pin "8") (pinfunction "FREQ_ADJ_8") (pintype "bidirectional"))
      (node (ref "R49") (pin "2") (pinfunction "2_2") (pintype "passive"))
    )
    (net (code "92") (name "Net-(IC8-GVDD_AB)") (class "Default")
      (node (ref "C85") (pin "2") (pinfunction "2_2") (pintype "passive"))
      (node (ref "IC8") (pin "1") (pinfunction "GVDD_AB_1") (pintype "bidirectional"))
      (node (ref "R52") (pin "2") (pinfunction "2_2") (pintype "passive"))
    )
    (net (code "93") (name "Net-(IC8-GVDD_CD)") (class "Default")
      (node (ref "C84") (pin "2") (pinfunction "2_2") (pintype "passive"))
      (node (ref "IC8") (pin "22") (pinfunction "GVDD_CD_22") (pintype "bidirectional"))
      (node (ref "R51") (pin "2") (pinfunction "2_2") (pintype "passive"))
    )
    (net (code "94") (name "Net-(IC8-OC_ADJ)") (class "Default")
      (node (ref "IC8") (pin "7") (pinfunction "OC_ADJ_7") (pintype "bidirectional"))
      (node (ref "R50") (pin "2") (pinfunction "2_2") (pintype "passive"))
    )
    (net (code "95") (name "Net-(IC8-OUT_A{slash}1)") (class "Default")
      (node (ref "C82") (pin "2") (pinfunction "2_2") (pintype "passive"))
      (node (ref "C83") (pin "1") (pinfunction "1_1") (pintype "passive"))
      (node (ref "IC8") (pin "32") (pinfunction "OUT_C_32") (pintype "bidirectional"))
      (node (ref "IC8") (pin "39") (pinfunction "OUT_A/1_39") (pintype "bidirectional"))
      (node (ref "IC8") (pin "40") (pinfunction "OUT_A/2_40") (pintype "bidirectional"))
      (node (ref "L3") (pin "3") (pinfunction "L2_1_3") (pintype "bidirectional"))
    )
    (net (code "96") (name "Net-(IC8-OUT_B)") (class "Default")
      (node (ref "C80") (pin "2") (pinfunction "2_2") (pintype "passive"))
      (node (ref "C81") (pin "1") (pinfunction "1_1") (pintype "passive"))
      (node (ref "IC8") (pin "27") (pinfunction "OUT_D/1_27") (pintype "bidirectional"))
      (node (ref "IC8") (pin "28") (pinfunction "OUT_D2_28") (pintype "bidirectional"))
      (node (ref "IC8") (pin "35") (pinfunction "OUT_B_35") (pintype "bidirectional"))
      (node (ref "L3") (pin "2") (pinfunction "L1_2_2") (pintype "bidirectional"))
    )
    (net (code "97") (name "Net-(IC8-VBG)") (class "Default")
      (node (ref "C68") (pin "2") (pinfunction "2_2") (pintype "passive"))
      (node (ref "IC8") (pin "20") (pinfunction "VBG_20") (pintype "bidirectional"))
    )
    (net (code "98") (name "Net-(JP1-Pad2)") (class "Default")
      (node (ref "JP1") (pin "2") (pinfunction "2_2") (pintype "passive"))
      (node (ref "R1") (pin "1") (pinfunction "1_1") (pintype "passive"))
    )
    (net (code "99") (name "Net-(JP1-Pad4)") (class "Default")
      (node (ref "JP1") (pin "4") (pinfunction "4_4") (pintype "passive"))
      (node (ref "R2") (pin "1") (pinfunction "1_1") (pintype "passive"))
    )
    (net (code "100") (name "Net-(JP1-Pad6)") (class "Default")
      (node (ref "JP1") (pin "6") (pinfunction "6_6") (pintype "passive"))
      (node (ref "R3") (pin "1") (pinfunction "1_1") (pintype "passive"))
    )
    (net (code "101") (name "Net-(JP1-Pad8)") (class "Default")
      (node (ref "JP1") (pin "8") (pinfunction "8_8") (pintype "passive"))
      (node (ref "R4") (pin "1") (pinfunction "1_1") (pintype "passive"))
    )
    (net (code "102") (name "Net-(JP1-Pad10)") (class "Default")
      (node (ref "JP1") (pin "10") (pinfunction "10_10") (pintype "passive"))
      (node (ref "R5") (pin "1") (pinfunction "1_1") (pintype "passive"))
    )
    (net (code "103") (name "Net-(JP1-Pad12)") (class "Default")
      (node (ref "JP1") (pin "12") (pinfunction "12_12") (pintype "passive"))
      (node (ref "R6") (pin "1") (pinfunction "1_1") (pintype "passive"))
    )
    (net (code "104") (name "Net-(JP1-Pad14)") (class "Default")
      (node (ref "JP1") (pin "14") (pinfunction "14_14") (pintype "passive"))
      (node (ref "R7") (pin "1") (pinfunction "1_1") (pintype "passive"))
    )
    (net (code "105") (name "Net-(JP1-Pad16)") (class "Default")
      (node (ref "JP1") (pin "16") (pinfunction "16_16") (pintype "passive"))
      (node (ref "R8") (pin "1") (pinfunction "1_1") (pintype "passive"))
    )
    (net (code "106") (name "Net-(JP1-Pad18)") (class "Default")
      (node (ref "JP1") (pin "18") (pinfunction "18_18") (pintype "passive"))
      (node (ref "R9") (pin "1") (pinfunction "1_1") (pintype "passive"))
    )
    (net (code "107") (name "Net-(JP1-Pad20)") (class "Default")
      (node (ref "JP1") (pin "20") (pinfunction "20_20") (pintype "passive"))
      (node (ref "R10") (pin "1") (pinfunction "1_1") (pintype "passive"))
    )
    (net (code "108") (name "Net-(JP1-Pad22)") (class "Default")
      (node (ref "JP1") (pin "22") (pinfunction "22_22") (pintype "passive"))
      (node (ref "R11") (pin "1") (pinfunction "1_1") (pintype "passive"))
    )
    (net (code "109") (name "Net-(JP1-Pad24)") (class "Default")
      (node (ref "JP1") (pin "24") (pinfunction "24_24") (pintype "passive"))
      (node (ref "R12") (pin "1") (pinfunction "1_1") (pintype "passive"))
    )
    (net (code "110") (name "Net-(R36-E)") (class "Default")
      (node (ref "R36") (pin "1") (pinfunction "E_1") (pintype "passive"))
      (node (ref "R58") (pin "1") (pinfunction "1_1") (pintype "passive"))
    )
    (net (code "111") (name "Net-(T1-D)") (class "Default")
      (node (ref "R38") (pin "1") (pinfunction "1_1") (pintype "passive"))
      (node (ref "T1") (pin "3") (pinfunction "D_3") (pintype "passive"))
      (node (ref "T2") (pin "1") (pinfunction "G_1") (pintype "passive"))
    )
    (net (code "112") (name "Net-(T1-G)") (class "Default")
      (node (ref "C43") (pin "1") (pinfunction "1_1") (pintype "passive"))
      (node (ref "C44") (pin "1") (pinfunction "1_1") (pintype "passive"))
      (node (ref "C45") (pin "1") (pinfunction "1_1") (pintype "passive"))
      (node (ref "D1") (pin "C") (pinfunction "C_C") (pintype "passive"))
      (node (ref "R37") (pin "1") (pinfunction "1_1") (pintype "passive"))
      (node (ref "T1") (pin "1") (pinfunction "G_1") (pintype "passive"))
    )
    (net (code "113") (name "Net-(U1-CAPM)") (class "Default")
      (node (ref "C4") (pin "2") (pinfunction "2_2") (pintype "passive"))
      (node (ref "U1") (pin "4") (pinfunction "CAPM_4") (pintype "passive"))
    )
    (net (code "114") (name "Net-(U1-CAPP)") (class "Default")
      (node (ref "C4") (pin "1") (pinfunction "1_1") (pintype "passive"))
      (node (ref "U1") (pin "2") (pinfunction "CAPP_2") (pintype "passive"))
    )
    (net (code "115") (name "Net-(U1-LDOO)") (class "Default")
      (node (ref "C10") (pin "1") (pinfunction "1_1") (pintype "passive"))
      (node (ref "C9") (pin "1") (pinfunction "1_1") (pintype "passive"))
      (node (ref "U1") (pin "18") (pinfunction "LDOO_18") (pintype "power_in"))
    )
    (net (code "116") (name "Net-(U1-OUTL)") (class "Default")
      (node (ref "R17") (pin "1") (pinfunction "1_1") (pintype "passive"))
      (node (ref "U1") (pin "6") (pinfunction "OUTL_6") (pintype "output"))
    )
    (net (code "117") (name "Net-(U1-OUTR)") (class "Default")
      (node (ref "R18") (pin "1") (pinfunction "1_1") (pintype "passive"))
      (node (ref "U1") (pin "7") (pinfunction "OUTR_7") (pintype "output"))
    )
    (net (code "118") (name "Net-(U1-VNEG)") (class "Default")
      (node (ref "C5") (pin "1") (pinfunction "1_1") (pintype "passive"))
      (node (ref "U1") (pin "5") (pinfunction "VNEG_5") (pintype "output"))
    )
    (net (code "119") (name "PCM_CLK") (class "Default")
      (node (ref "BT1") (pin "7") (pinfunction "PIO_20/PCM_CLK_7") (pintype "bidirectional"))
      (node (ref "U1") (pin "13") (pinfunction "BCK_13") (pintype "input"))
    )
    (net (code "120") (name "PCM_OUT") (class "Default")
      (node (ref "BT1") (pin "9") (pinfunction "PIO_18/PCM_OUT_9") (pintype "bidirectional"))
      (node (ref "U1") (pin "14") (pinfunction "DIN_14") (pintype "input"))
    )
    (net (code "121") (name "PCM_SYNC") (class "Default")
      (node (ref "BT1") (pin "8") (pinfunction "PIO_19/PCM_SYNC_8") (pintype "bidirectional"))
      (node (ref "U1") (pin "15") (pinfunction "LRCK_15") (pintype "input"))
    )
    (net (code "122") (name "PIO0") (class "Default")
      (node (ref "BT1") (pin "23") (pinfunction "PIO_0_23") (pintype "bidirectional"))
      (node (ref "R4") (pin "2") (pinfunction "2_2") (pintype "passive"))
    )
    (net (code "123") (name "PIO1") (class "Default")
      (node (ref "BT1") (pin "24") (pinfunction "PIO_1_24") (pintype "bidirectional"))
      (node (ref "R5") (pin "2") (pinfunction "2_2") (pintype "passive"))
    )
    (net (code "124") (name "PIO2") (class "Default")
      (node (ref "BT1") (pin "25") (pinfunction "PIO_2_25") (pintype "bidirectional"))
      (node (ref "R6") (pin "2") (pinfunction "2_2") (pintype "passive"))
    )
    (net (code "125") (name "PIO3") (class "Default")
      (node (ref "BT1") (pin "30") (pinfunction "PIO_3_30") (pintype "bidirectional"))
      (node (ref "R7") (pin "2") (pinfunction "2_2") (pintype "passive"))
    )
    (net (code "126") (name "PIO4") (class "Default")
      (node (ref "BT1") (pin "31") (pinfunction "PIO_4_31") (pintype "bidirectional"))
      (node (ref "R8") (pin "2") (pinfunction "2_2") (pintype "passive"))
    )
    (net (code "127") (name "PIO5") (class "Default")
      (node (ref "BT1") (pin "32") (pinfunction "PIO_5_32") (pintype "bidirectional"))
      (node (ref "R9") (pin "2") (pinfunction "2_2") (pintype "passive"))
    )
    (net (code "128") (name "PIO6") (class "Default")
      (node (ref "BT1") (pin "33") (pinfunction "PIO_6_33") (pintype "bidirectional"))
      (node (ref "R10") (pin "2") (pinfunction "2_2") (pintype "passive"))
    )
    (net (code "129") (name "PIO7") (class "Default")
      (node (ref "BT1") (pin "34") (pinfunction "PIO_7_34") (pintype "bidirectional"))
      (node (ref "R11") (pin "2") (pinfunction "2_2") (pintype "passive"))
    )
    (net (code "130") (name "PIO10") (class "Default")
      (node (ref "BT1") (pin "35") (pinfunction "PIO_10_35") (pintype "bidirectional"))
      (node (ref "SJ2") (pin "2") (pinfunction "2_2") (pintype "passive"))
    )
    (net (code "131") (name "PIO11") (class "Default")
      (node (ref "BT1") (pin "36") (pinfunction "PIO_11_36") (pintype "bidirectional"))
      (node (ref "SJ1") (pin "1") (pinfunction "1_1") (pintype "passive"))
    )
    (net (code "132") (name "PIO12") (class "Default")
      (node (ref "BT1") (pin "37") (pinfunction "PIO_12_37") (pintype "bidirectional"))
      (node (ref "SJ3") (pin "1") (pinfunction "1_1") (pintype "passive"))
    )
    (net (code "133") (name "PIO13") (class "Default")
      (node (ref "BT1") (pin "38") (pinfunction "PIO_13_38") (pintype "bidirectional"))
    )
    (net (code "134") (name "PIO14") (class "Default")
      (node (ref "BT1") (pin "39") (pinfunction "PIO_14_39") (pintype "bidirectional"))
    )
    (net (code "135") (name "PIO15") (class "Default")
      (node (ref "BT1") (pin "40") (pinfunction "PIO_15_40") (pintype "bidirectional"))
      (node (ref "U1") (pin "17") (pinfunction "XSMT_17") (pintype "input"))
    )
    (net (code "136") (name "PWR") (class "Default")
      (node (ref "BT1") (pin "43") (pinfunction "PWR_43") (pintype "bidirectional"))
      (node (ref "R12") (pin "2") (pinfunction "2_2") (pintype "passive"))
    )
    (net (code "137") (name "RN") (class "Default")
      (node (ref "C47") (pin "2") (pinfunction "2_2") (pintype "passive"))
      (node (ref "C53") (pin "2") (pinfunction "2_2") (pintype "passive"))
      (node (ref "C59") (pin "2") (pinfunction "2_2") (pintype "passive"))
      (node (ref "L1") (pin "4") (pinfunction "L2_2_4") (pintype "bidirectional"))
      (node (ref "SPK") (pin "P$1") (pinfunction "1_P$1") (pintype "bidirectional"))
    )
    (net (code "138") (name "RP") (class "Default")
      (node (ref "C46") (pin "1") (pinfunction "1_1") (pintype "passive"))
      (node (ref "C52") (pin "1") (pinfunction "1_1") (pintype "passive"))
      (node (ref "C58") (pin "1") (pinfunction "1_1") (pintype "passive"))
      (node (ref "L1") (pin "1") (pinfunction "L1_1_1") (pintype "bidirectional"))
      (node (ref "SPK") (pin "P$6") (pinfunction "6_P$6") (pintype "bidirectional"))
    )
    (net (code "139") (name "SPI_CLK") (class "Default")
      (node (ref "BT1") (pin "11") (pinfunction "SPI_CLK_11") (pintype "bidirectional"))
      (node (ref "JP2") (pin "6") (pinfunction "6_6") (pintype "passive"))
    )
    (net (code "140") (name "SPI_CSB") (class "Default")
      (node (ref "BT1") (pin "13") (pinfunction "SPI_CSB_13") (pintype "bidirectional"))
      (node (ref "JP2") (pin "4") (pinfunction "4_4") (pintype "passive"))
    )
    (net (code "141") (name "SPI_MISO") (class "Default")
      (node (ref "BT1") (pin "14") (pinfunction "SPI_MISO_14") (pintype "bidirectional"))
      (node (ref "JP2") (pin "10") (pinfunction "10_10") (pintype "passive"))
    )
    (net (code "142") (name "SPI_MOSI") (class "Default")
      (node (ref "BT1") (pin "12") (pinfunction "SPI_MOSI_12") (pintype "bidirectional"))
      (node (ref "JP2") (pin "8") (pinfunction "8_8") (pintype "passive"))
    )
    (net (code "143") (name "SPKR_LN") (class "Default")
      (node (ref "BT1") (pin "58") (pinfunction "SPKR_LN_58") (pintype "bidirectional"))
      (node (ref "IC3") (pin "12") (pinfunction "+IN_12") (pintype "input"))
    )
    (net (code "144") (name "SPKR_LP") (class "Default")
      (node (ref "BT1") (pin "59") (pinfunction "SPKR_LP_59") (pintype "bidirectional"))
      (node (ref "C41") (pin "1") (pinfunction "1_1") (pintype "passive"))
      (node (ref "IC3") (pin "10") (pinfunction "+IN_10") (pintype "input"))
    )
    (net (code "145") (name "SPKR_RN") (class "Default")
      (node (ref "BT1") (pin "60") (pinfunction "SPKR_RN_60") (pintype "bidirectional"))
      (node (ref "IC3") (pin "5") (pinfunction "+IN_5") (pintype "input"))
    )
    (net (code "146") (name "SPKR_RP") (class "Default")
      (node (ref "BT1") (pin "61") (pinfunction "SPKR_RP_61") (pintype "bidirectional"))
      (node (ref "IC3") (pin "3") (pinfunction "+IN_3") (pintype "input"))
    )
    (net (code "147") (name "SPKR_SN") (class "Default")
      (node (ref "C16") (pin "1") (pinfunction "1_1") (pintype "passive"))
      (node (ref "C31") (pin "2") (pinfunction "2_2") (pintype "passive"))
      (node (ref "R18") (pin "2") (pinfunction "2_2") (pintype "passive"))
    )
    (net (code "148") (name "SPKR_SP") (class "Default")
      (node (ref "C17") (pin "1") (pinfunction "1_1") (pintype "passive"))
      (node (ref "C30") (pin "2") (pinfunction "2_2") (pintype "passive"))
      (node (ref "R17") (pin "2") (pinfunction "2_2") (pintype "passive"))
    )
    (net (code "149") (name "SUBN") (class "Default")
      (node (ref "C51") (pin "2") (pinfunction "2_2") (pintype "passive"))
      (node (ref "C57") (pin "2") (pinfunction "2_2") (pintype "passive"))
      (node (ref "C63") (pin "2") (pinfunction "2_2") (pintype "passive"))
      (node (ref "L3") (pin "4") (pinfunction "L2_2_4") (pintype "bidirectional"))
      (node (ref "SPK") (pin "P$3") (pinfunction "3_P$3") (pintype "bidirectional"))
    )
    (net (code "150") (name "SUBP") (class "Default")
      (node (ref "C50") (pin "1") (pinfunction "1_1") (pintype "passive"))
      (node (ref "C56") (pin "1") (pinfunction "1_1") (pintype "passive"))
      (node (ref "C62") (pin "1") (pinfunction "1_1") (pintype "passive"))
      (node (ref "L3") (pin "1") (pinfunction "L1_1_1") (pintype "bidirectional"))
      (node (ref "SPK") (pin "P$4") (pinfunction "4_P$4") (pintype "bidirectional"))
    )
    (net (code "151") (name "VAMP") (class "Default")
      (node (ref "C101") (pin "+") (pinfunction "+_+") (pintype "passive"))
      (node (ref "C64") (pin "1") (pinfunction "1_1") (pintype "passive"))
      (node (ref "C65") (pin "1") (pinfunction "1_1") (pintype "passive"))
      (node (ref "C66") (pin "1") (pinfunction "1_1") (pintype "passive"))
      (node (ref "C67") (pin "1") (pinfunction "1_1") (pintype "passive"))
      (node (ref "C72") (pin "+") (pinfunction "+_+") (pintype "passive"))
      (node (ref "C73") (pin "+") (pinfunction "+_+") (pintype "passive"))
      (node (ref "C74") (pin "+") (pinfunction "+_+") (pintype "passive"))
      (node (ref "C75") (pin "+") (pinfunction "+_+") (pintype "passive"))
      (node (ref "C94") (pin "1") (pinfunction "1_1") (pintype "passive"))
      (node (ref "C95") (pin "1") (pinfunction "1_1") (pintype "passive"))
      (node (ref "C96") (pin "1") (pinfunction "1_1") (pintype "passive"))
      (node (ref "C97") (pin "1") (pinfunction "1_1") (pintype "passive"))
      (node (ref "DPSU") (pin "P$6") (pinfunction "6_P$6") (pintype "bidirectional"))
      (node (ref "IC7") (pin "29") (pinfunction "PVDD_CD/1_29") (pintype "bidirectional"))
      (node (ref "IC7") (pin "30") (pinfunction "PVDD_CD/2_30") (pintype "bidirectional"))
      (node (ref "IC7") (pin "31") (pinfunction "PVDD_CD/3_31") (pintype "bidirectional"))
      (node (ref "IC7") (pin "36") (pinfunction "PVDD_AB/1_36") (pintype "bidirectional"))
      (node (ref "IC7") (pin "37") (pinfunction "PVDD_AB/2_37") (pintype "bidirectional"))
      (node (ref "IC7") (pin "38") (pinfunction "PVDD_AB/3_38") (pintype "bidirectional"))
      (node (ref "IC8") (pin "29") (pinfunction "PVDD_CD/1_29") (pintype "bidirectional"))
      (node (ref "IC8") (pin "30") (pinfunction "PVDD_CD/2_30") (pintype "bidirectional"))
      (node (ref "IC8") (pin "31") (pinfunction "PVDD_CD/3_31") (pintype "bidirectional"))
      (node (ref "IC8") (pin "36") (pinfunction "PVDD_AB/1_36") (pintype "bidirectional"))
      (node (ref "IC8") (pin "37") (pinfunction "PVDD_AB/2_37") (pintype "bidirectional"))
      (node (ref "IC8") (pin "38") (pinfunction "PVDD_AB/3_38") (pintype "bidirectional"))
      (node (ref "VAMP") (pin "1") (pinfunction "P_1") (pintype "passive"))
    )
    (net (code "152") (name "unconnected-(BT1-+1V8-Pad48)") (class "Default")
      (node (ref "BT1") (pin "48") (pinfunction "+1V8_48") (pintype "bidirectional"))
    )
    (net (code "153") (name "unconnected-(BT1-3V3_OUT-Pad49)") (class "Default")
      (node (ref "BT1") (pin "49") (pinfunction "3V3_OUT_49") (pintype "bidirectional"))
    )
    (net (code "154") (name "unconnected-(BT1-AIO_0-Pad62)") (class "Default")
      (node (ref "BT1") (pin "62") (pinfunction "AIO_0_62") (pintype "bidirectional"))
    )
    (net (code "155") (name "unconnected-(BT1-AIO_1-Pad5)") (class "Default")
      (node (ref "BT1") (pin "5") (pinfunction "AIO_1_5") (pintype "bidirectional"))
    )
    (net (code "156") (name "unconnected-(BT1-BT_RESET-Pad10)") (class "Default")
      (node (ref "BT1") (pin "10") (pinfunction "BT_RESET_10") (pintype "bidirectional"))
    )
    (net (code "157") (name "unconnected-(BT1-CAP_SENSE_0-Pad3)") (class "Default")
      (node (ref "BT1") (pin "3") (pinfunction "CAP_SENSE_0_3") (pintype "bidirectional"))
    )
    (net (code "158") (name "unconnected-(BT1-CAP_SENSE_1-Pad66)") (class "Default")
      (node (ref "BT1") (pin "66") (pinfunction "CAP_SENSE_1_66") (pintype "bidirectional"))
    )
    (net (code "159") (name "unconnected-(BT1-CAP_SENSE_2-Pad2)") (class "Default")
      (node (ref "BT1") (pin "2") (pinfunction "CAP_SENSE_2_2") (pintype "bidirectional"))
    )
    (net (code "160") (name "unconnected-(BT1-CAP_SENSE_3-Pad67)") (class "Default")
      (node (ref "BT1") (pin "67") (pinfunction "CAP_SENSE_3_67") (pintype "bidirectional"))
    )
    (net (code "161") (name "unconnected-(BT1-CAP_SENSE_4-Pad68)") (class "Default")
      (node (ref "BT1") (pin "68") (pinfunction "CAP_SENSE_4_68") (pintype "bidirectional"))
    )
    (net (code "162") (name "unconnected-(BT1-CAP_SENSE_5-Pad1)") (class "Default")
      (node (ref "BT1") (pin "1") (pinfunction "CAP_SENSE_5_1") (pintype "bidirectional"))
    )
    (net (code "163") (name "unconnected-(BT1-CHG_EXT-Pad47)") (class "Default")
      (node (ref "BT1") (pin "47") (pinfunction "CHG_EXT_47") (pintype "bidirectional"))
    )
    (net (code "164") (name "unconnected-(BT1-MIC_BIAS_A-Pad54)") (class "Default")
      (node (ref "BT1") (pin "54") (pinfunction "MIC_BIAS_A_54") (pintype "bidirectional"))
    )
    (net (code "165") (name "unconnected-(BT1-MIC_BIAS_B-Pad53)") (class "Default")
      (node (ref "BT1") (pin "53") (pinfunction "MIC_BIAS_B_53") (pintype "bidirectional"))
    )
    (net (code "166") (name "unconnected-(BT1-PIO_17{slash}PCM_IN-Pad6)") (class "Default")
      (node (ref "BT1") (pin "6") (pinfunction "PIO_17/PCM_IN_6") (pintype "bidirectional"))
    )
    (net (code "167") (name "unconnected-(BT1-UART_CTS-Pad16)") (class "Default")
      (node (ref "BT1") (pin "16") (pinfunction "UART_CTS_16") (pintype "bidirectional"))
    )
    (net (code "168") (name "unconnected-(BT1-UART_RTS-Pad15)") (class "Default")
      (node (ref "BT1") (pin "15") (pinfunction "UART_RTS_15") (pintype "bidirectional"))
    )
    (net (code "169") (name "unconnected-(BT1-UART_RX-Pad17)") (class "Default")
      (node (ref "BT1") (pin "17") (pinfunction "UART_RX_17") (pintype "bidirectional"))
    )
    (net (code "170") (name "unconnected-(BT1-UART_TX-Pad18)") (class "Default")
      (node (ref "BT1") (pin "18") (pinfunction "UART_TX_18") (pintype "bidirectional"))
    )
    (net (code "171") (name "unconnected-(BT1-USB_DN-Pad28)") (class "Default")
      (node (ref "BT1") (pin "28") (pinfunction "USB_DN_28") (pintype "bidirectional"))
    )
    (net (code "172") (name "unconnected-(BT1-USB_DP-Pad27)") (class "Default")
      (node (ref "BT1") (pin "27") (pinfunction "USB_DP_27") (pintype "bidirectional"))
    )
    (net (code "173") (name "unconnected-(BT1-VBUS-Pad46)") (class "Default")
      (node (ref "BT1") (pin "46") (pinfunction "VBUS_46") (pintype "bidirectional"))
    )
    (net (code "174") (name "unconnected-(BT1-VDD_USB-Pad29)") (class "Default")
      (node (ref "BT1") (pin "29") (pinfunction "VDD_USB_29") (pintype "bidirectional"))
    )
    (net (code "175") (name "unconnected-(IC7-OSC_IOM-Pad9)") (class "Default")
      (node (ref "IC7") (pin "9") (pinfunction "OSC_IOM_9") (pintype "bidirectional"))
    )
    (net (code "176") (name "unconnected-(IC7-OSC_IOP-Pad10)") (class "Default")
      (node (ref "IC7") (pin "10") (pinfunction "OSC_IOP_10") (pintype "bidirectional"))
    )
    (net (code "177") (name "unconnected-(IC7-{slash}CLIP_OTW-Pad21)") (class "Default")
      (node (ref "IC7") (pin "21") (pinfunction "/CLIP_OTW_21") (pintype "bidirectional"))
    )
    (net (code "178") (name "unconnected-(IC7-{slash}FAULT-Pad19)") (class "Default")
      (node (ref "IC7") (pin "19") (pinfunction "/FAULT_19") (pintype "bidirectional"))
    )
    (net (code "179") (name "unconnected-(IC8-OSC_IOM-Pad9)") (class "Default")
      (node (ref "IC8") (pin "9") (pinfunction "OSC_IOM_9") (pintype "bidirectional"))
    )
    (net (code "180") (name "unconnected-(IC8-OSC_IOP-Pad10)") (class "Default")
      (node (ref "IC8") (pin "10") (pinfunction "OSC_IOP_10") (pintype "bidirectional"))
    )
    (net (code "181") (name "unconnected-(IC8-{slash}CLIP_OTW-Pad21)") (class "Default")
      (node (ref "IC8") (pin "21") (pinfunction "/CLIP_OTW_21") (pintype "bidirectional"))
    )
    (net (code "182") (name "unconnected-(IC8-{slash}FAULT-Pad19)") (class "Default")
      (node (ref "IC8") (pin "19") (pinfunction "/FAULT_19") (pintype "bidirectional"))
    )
    (net (code "183") (name "unconnected-(JP2-Pad5)") (class "Default")
      (node (ref "JP2") (pin "5") (pinfunction "5_5") (pintype "passive"))
    )
    (net (code "184") (name "unconnected-(JP2-Pad7)") (class "Default")
      (node (ref "JP2") (pin "7") (pinfunction "7_7") (pintype "passive"))
    )
    (net (code "185") (name "unconnected-(JP2-Pad9)") (class "Default")
      (node (ref "JP2") (pin "9") (pinfunction "9_9") (pintype "passive"))
    )
  )
)
